# candle.net
KiCad netlist of a schematic drawn in EAGLE
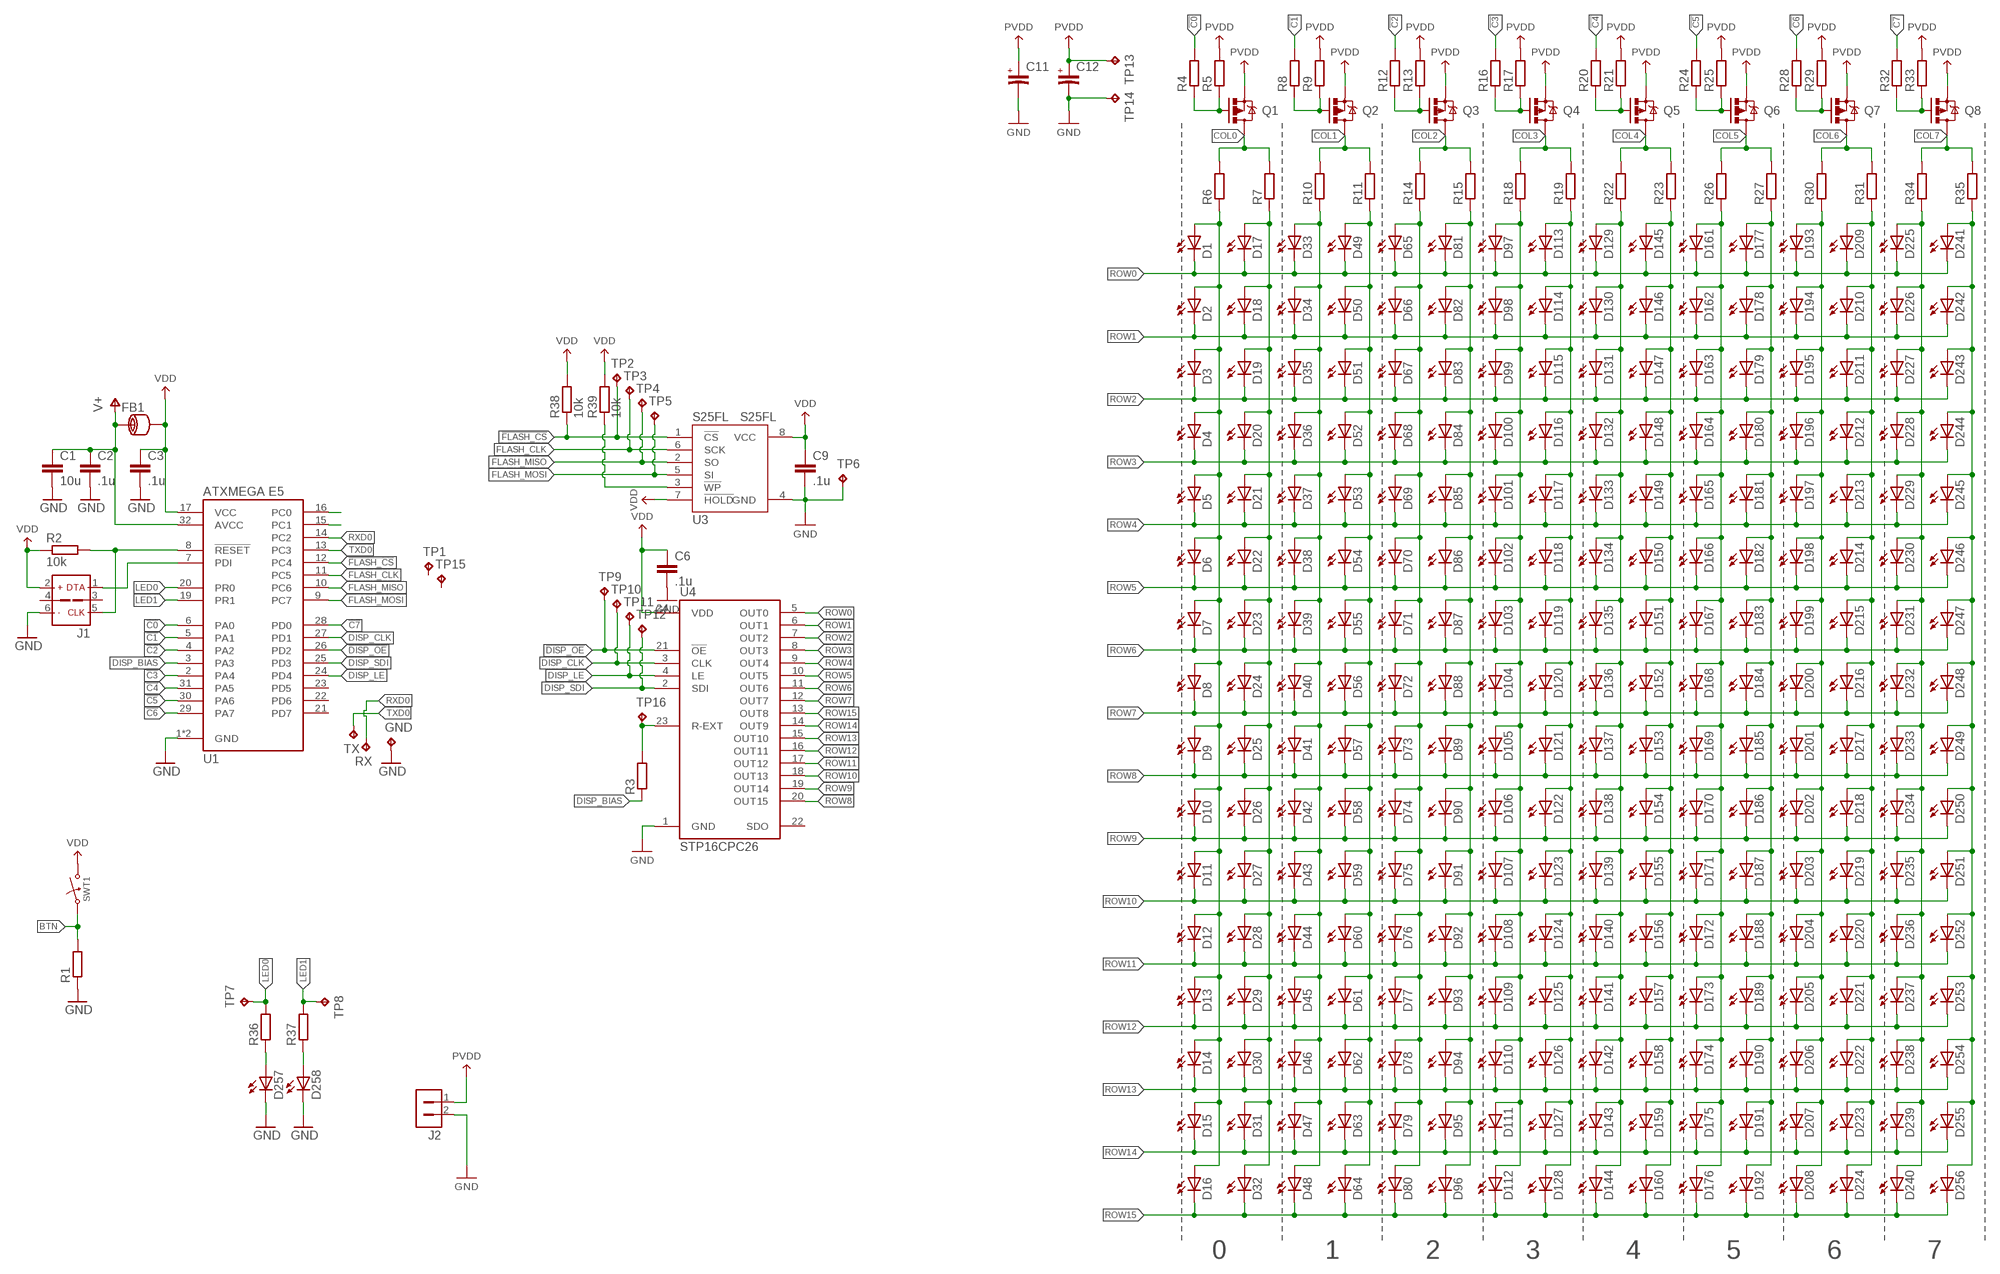
[diagram p0: schematic, sheet 1]

(export (version "E")
  (design (tool "Eeschema 10.0.6"))
  (components
    (comp (ref "C1")
      (value "10u")
      (footprint "eagle-import:0805")
      (libsource (lib "eagle-import") (part "C_0805"))
    )
    (comp (ref "C2")
      (value ".1u")
      (footprint "eagle-import:0805")
      (libsource (lib "eagle-import") (part "C_0805"))
    )
    (comp (ref "C3")
      (value ".1u")
      (footprint "eagle-import:0805")
      (libsource (lib "eagle-import") (part "C_0805"))
    )
    (comp (ref "C6")
      (value ".1u")
      (footprint "eagle-import:0805")
      (libsource (lib "eagle-import") (part "C_0805"))
    )
    (comp (ref "C9")
      (value ".1u")
      (footprint "eagle-import:0805")
      (libsource (lib "eagle-import") (part "C_0805"))
    )
    (comp (ref "C11")
      (value "C_POL_1206")
      (footprint "eagle-import:1206_POL")
      (libsource (lib "eagle-import") (part "C_POL_1206"))
    )
    (comp (ref "C12")
      (value "C_POL_1206")
      (footprint "eagle-import:1206_POL")
      (libsource (lib "eagle-import") (part "C_POL_1206"))
    )
    (comp (ref "D1")
      (value "LED_0805")
      (footprint "eagle-import:0805_LED")
      (libsource (lib "eagle-import") (part "LED_0805"))
    )
    (comp (ref "D2")
      (value "LED_0805")
      (footprint "eagle-import:0805_LED")
      (libsource (lib "eagle-import") (part "LED_0805"))
    )
    (comp (ref "D3")
      (value "LED_0805")
      (footprint "eagle-import:0805_LED")
      (libsource (lib "eagle-import") (part "LED_0805"))
    )
    (comp (ref "D4")
      (value "LED_0805")
      (footprint "eagle-import:0805_LED")
      (libsource (lib "eagle-import") (part "LED_0805"))
    )
    (comp (ref "D5")
      (value "LED_0805")
      (footprint "eagle-import:0805_LED")
      (libsource (lib "eagle-import") (part "LED_0805"))
    )
    (comp (ref "D6")
      (value "LED_0805")
      (footprint "eagle-import:0805_LED")
      (libsource (lib "eagle-import") (part "LED_0805"))
    )
    (comp (ref "D7")
      (value "LED_0805")
      (footprint "eagle-import:0805_LED")
      (libsource (lib "eagle-import") (part "LED_0805"))
    )
    (comp (ref "D8")
      (value "LED_0805")
      (footprint "eagle-import:0805_LED")
      (libsource (lib "eagle-import") (part "LED_0805"))
    )
    (comp (ref "D9")
      (value "LED_0805")
      (footprint "eagle-import:0805_LED")
      (libsource (lib "eagle-import") (part "LED_0805"))
    )
    (comp (ref "D10")
      (value "LED_0805")
      (footprint "eagle-import:0805_LED")
      (libsource (lib "eagle-import") (part "LED_0805"))
    )
    (comp (ref "D11")
      (value "LED_0805")
      (footprint "eagle-import:0805_LED")
      (libsource (lib "eagle-import") (part "LED_0805"))
    )
    (comp (ref "D12")
      (value "LED_0805")
      (footprint "eagle-import:0805_LED")
      (libsource (lib "eagle-import") (part "LED_0805"))
    )
    (comp (ref "D13")
      (value "LED_0805")
      (footprint "eagle-import:0805_LED")
      (libsource (lib "eagle-import") (part "LED_0805"))
    )
    (comp (ref "D14")
      (value "LED_0805")
      (footprint "eagle-import:0805_LED")
      (libsource (lib "eagle-import") (part "LED_0805"))
    )
    (comp (ref "D15")
      (value "LED_0805")
      (footprint "eagle-import:0805_LED")
      (libsource (lib "eagle-import") (part "LED_0805"))
    )
    (comp (ref "D16")
      (value "LED_0805")
      (footprint "eagle-import:0805_LED")
      (libsource (lib "eagle-import") (part "LED_0805"))
    )
    (comp (ref "D17")
      (value "LED_0805")
      (footprint "eagle-import:0805_LED")
      (libsource (lib "eagle-import") (part "LED_0805"))
    )
    (comp (ref "D18")
      (value "LED_0805")
      (footprint "eagle-import:0805_LED")
      (libsource (lib "eagle-import") (part "LED_0805"))
    )
    (comp (ref "D19")
      (value "LED_0805")
      (footprint "eagle-import:0805_LED")
      (libsource (lib "eagle-import") (part "LED_0805"))
    )
    (comp (ref "D20")
      (value "LED_0805")
      (footprint "eagle-import:0805_LED")
      (libsource (lib "eagle-import") (part "LED_0805"))
    )
    (comp (ref "D21")
      (value "LED_0805")
      (footprint "eagle-import:0805_LED")
      (libsource (lib "eagle-import") (part "LED_0805"))
    )
    (comp (ref "D22")
      (value "LED_0805")
      (footprint "eagle-import:0805_LED")
      (libsource (lib "eagle-import") (part "LED_0805"))
    )
    (comp (ref "D23")
      (value "LED_0805")
      (footprint "eagle-import:0805_LED")
      (libsource (lib "eagle-import") (part "LED_0805"))
    )
    (comp (ref "D24")
      (value "LED_0805")
      (footprint "eagle-import:0805_LED")
      (libsource (lib "eagle-import") (part "LED_0805"))
    )
    (comp (ref "D25")
      (value "LED_0805")
      (footprint "eagle-import:0805_LED")
      (libsource (lib "eagle-import") (part "LED_0805"))
    )
    (comp (ref "D26")
      (value "LED_0805")
      (footprint "eagle-import:0805_LED")
      (libsource (lib "eagle-import") (part "LED_0805"))
    )
    (comp (ref "D27")
      (value "LED_0805")
      (footprint "eagle-import:0805_LED")
      (libsource (lib "eagle-import") (part "LED_0805"))
    )
    (comp (ref "D28")
      (value "LED_0805")
      (footprint "eagle-import:0805_LED")
      (libsource (lib "eagle-import") (part "LED_0805"))
    )
    (comp (ref "D29")
      (value "LED_0805")
      (footprint "eagle-import:0805_LED")
      (libsource (lib "eagle-import") (part "LED_0805"))
    )
    (comp (ref "D30")
      (value "LED_0805")
      (footprint "eagle-import:0805_LED")
      (libsource (lib "eagle-import") (part "LED_0805"))
    )
    (comp (ref "D31")
      (value "LED_0805")
      (footprint "eagle-import:0805_LED")
      (libsource (lib "eagle-import") (part "LED_0805"))
    )
    (comp (ref "D32")
      (value "LED_0805")
      (footprint "eagle-import:0805_LED")
      (libsource (lib "eagle-import") (part "LED_0805"))
    )
    (comp (ref "D33")
      (value "LED_0805")
      (footprint "eagle-import:0805_LED")
      (libsource (lib "eagle-import") (part "LED_0805"))
    )
    (comp (ref "D34")
      (value "LED_0805")
      (footprint "eagle-import:0805_LED")
      (libsource (lib "eagle-import") (part "LED_0805"))
    )
    (comp (ref "D35")
      (value "LED_0805")
      (footprint "eagle-import:0805_LED")
      (libsource (lib "eagle-import") (part "LED_0805"))
    )
    (comp (ref "D36")
      (value "LED_0805")
      (footprint "eagle-import:0805_LED")
      (libsource (lib "eagle-import") (part "LED_0805"))
    )
    (comp (ref "D37")
      (value "LED_0805")
      (footprint "eagle-import:0805_LED")
      (libsource (lib "eagle-import") (part "LED_0805"))
    )
    (comp (ref "D38")
      (value "LED_0805")
      (footprint "eagle-import:0805_LED")
      (libsource (lib "eagle-import") (part "LED_0805"))
    )
    (comp (ref "D39")
      (value "LED_0805")
      (footprint "eagle-import:0805_LED")
      (libsource (lib "eagle-import") (part "LED_0805"))
    )
    (comp (ref "D40")
      (value "LED_0805")
      (footprint "eagle-import:0805_LED")
      (libsource (lib "eagle-import") (part "LED_0805"))
    )
    (comp (ref "D41")
      (value "LED_0805")
      (footprint "eagle-import:0805_LED")
      (libsource (lib "eagle-import") (part "LED_0805"))
    )
    (comp (ref "D42")
      (value "LED_0805")
      (footprint "eagle-import:0805_LED")
      (libsource (lib "eagle-import") (part "LED_0805"))
    )
    (comp (ref "D43")
      (value "LED_0805")
      (footprint "eagle-import:0805_LED")
      (libsource (lib "eagle-import") (part "LED_0805"))
    )
    (comp (ref "D44")
      (value "LED_0805")
      (footprint "eagle-import:0805_LED")
      (libsource (lib "eagle-import") (part "LED_0805"))
    )
    (comp (ref "D45")
      (value "LED_0805")
      (footprint "eagle-import:0805_LED")
      (libsource (lib "eagle-import") (part "LED_0805"))
    )
    (comp (ref "D46")
      (value "LED_0805")
      (footprint "eagle-import:0805_LED")
      (libsource (lib "eagle-import") (part "LED_0805"))
    )
    (comp (ref "D47")
      (value "LED_0805")
      (footprint "eagle-import:0805_LED")
      (libsource (lib "eagle-import") (part "LED_0805"))
    )
    (comp (ref "D48")
      (value "LED_0805")
      (footprint "eagle-import:0805_LED")
      (libsource (lib "eagle-import") (part "LED_0805"))
    )
    (comp (ref "D49")
      (value "LED_0805")
      (footprint "eagle-import:0805_LED")
      (libsource (lib "eagle-import") (part "LED_0805"))
    )
    (comp (ref "D50")
      (value "LED_0805")
      (footprint "eagle-import:0805_LED")
      (libsource (lib "eagle-import") (part "LED_0805"))
    )
    (comp (ref "D51")
      (value "LED_0805")
      (footprint "eagle-import:0805_LED")
      (libsource (lib "eagle-import") (part "LED_0805"))
    )
    (comp (ref "D52")
      (value "LED_0805")
      (footprint "eagle-import:0805_LED")
      (libsource (lib "eagle-import") (part "LED_0805"))
    )
    (comp (ref "D53")
      (value "LED_0805")
      (footprint "eagle-import:0805_LED")
      (libsource (lib "eagle-import") (part "LED_0805"))
    )
    (comp (ref "D54")
      (value "LED_0805")
      (footprint "eagle-import:0805_LED")
      (libsource (lib "eagle-import") (part "LED_0805"))
    )
    (comp (ref "D55")
      (value "LED_0805")
      (footprint "eagle-import:0805_LED")
      (libsource (lib "eagle-import") (part "LED_0805"))
    )
    (comp (ref "D56")
      (value "LED_0805")
      (footprint "eagle-import:0805_LED")
      (libsource (lib "eagle-import") (part "LED_0805"))
    )
    (comp (ref "D57")
      (value "LED_0805")
      (footprint "eagle-import:0805_LED")
      (libsource (lib "eagle-import") (part "LED_0805"))
    )
    (comp (ref "D58")
      (value "LED_0805")
      (footprint "eagle-import:0805_LED")
      (libsource (lib "eagle-import") (part "LED_0805"))
    )
    (comp (ref "D59")
      (value "LED_0805")
      (footprint "eagle-import:0805_LED")
      (libsource (lib "eagle-import") (part "LED_0805"))
    )
    (comp (ref "D60")
      (value "LED_0805")
      (footprint "eagle-import:0805_LED")
      (libsource (lib "eagle-import") (part "LED_0805"))
    )
    (comp (ref "D61")
      (value "LED_0805")
      (footprint "eagle-import:0805_LED")
      (libsource (lib "eagle-import") (part "LED_0805"))
    )
    (comp (ref "D62")
      (value "LED_0805")
      (footprint "eagle-import:0805_LED")
      (libsource (lib "eagle-import") (part "LED_0805"))
    )
    (comp (ref "D63")
      (value "LED_0805")
      (footprint "eagle-import:0805_LED")
      (libsource (lib "eagle-import") (part "LED_0805"))
    )
    (comp (ref "D64")
      (value "LED_0805")
      (footprint "eagle-import:0805_LED")
      (libsource (lib "eagle-import") (part "LED_0805"))
    )
    (comp (ref "D65")
      (value "LED_0805")
      (footprint "eagle-import:0805_LED")
      (libsource (lib "eagle-import") (part "LED_0805"))
    )
    (comp (ref "D66")
      (value "LED_0805")
      (footprint "eagle-import:0805_LED")
      (libsource (lib "eagle-import") (part "LED_0805"))
    )
    (comp (ref "D67")
      (value "LED_0805")
      (footprint "eagle-import:0805_LED")
      (libsource (lib "eagle-import") (part "LED_0805"))
    )
    (comp (ref "D68")
      (value "LED_0805")
      (footprint "eagle-import:0805_LED")
      (libsource (lib "eagle-import") (part "LED_0805"))
    )
    (comp (ref "D69")
      (value "LED_0805")
      (footprint "eagle-import:0805_LED")
      (libsource (lib "eagle-import") (part "LED_0805"))
    )
    (comp (ref "D70")
      (value "LED_0805")
      (footprint "eagle-import:0805_LED")
      (libsource (lib "eagle-import") (part "LED_0805"))
    )
    (comp (ref "D71")
      (value "LED_0805")
      (footprint "eagle-import:0805_LED")
      (libsource (lib "eagle-import") (part "LED_0805"))
    )
    (comp (ref "D72")
      (value "LED_0805")
      (footprint "eagle-import:0805_LED")
      (libsource (lib "eagle-import") (part "LED_0805"))
    )
    (comp (ref "D73")
      (value "LED_0805")
      (footprint "eagle-import:0805_LED")
      (libsource (lib "eagle-import") (part "LED_0805"))
    )
    (comp (ref "D74")
      (value "LED_0805")
      (footprint "eagle-import:0805_LED")
      (libsource (lib "eagle-import") (part "LED_0805"))
    )
    (comp (ref "D75")
      (value "LED_0805")
      (footprint "eagle-import:0805_LED")
      (libsource (lib "eagle-import") (part "LED_0805"))
    )
    (comp (ref "D76")
      (value "LED_0805")
      (footprint "eagle-import:0805_LED")
      (libsource (lib "eagle-import") (part "LED_0805"))
    )
    (comp (ref "D77")
      (value "LED_0805")
      (footprint "eagle-import:0805_LED")
      (libsource (lib "eagle-import") (part "LED_0805"))
    )
    (comp (ref "D78")
      (value "LED_0805")
      (footprint "eagle-import:0805_LED")
      (libsource (lib "eagle-import") (part "LED_0805"))
    )
    (comp (ref "D79")
      (value "LED_0805")
      (footprint "eagle-import:0805_LED")
      (libsource (lib "eagle-import") (part "LED_0805"))
    )
    (comp (ref "D80")
      (value "LED_0805")
      (footprint "eagle-import:0805_LED")
      (libsource (lib "eagle-import") (part "LED_0805"))
    )
    (comp (ref "D81")
      (value "LED_0805")
      (footprint "eagle-import:0805_LED")
      (libsource (lib "eagle-import") (part "LED_0805"))
    )
    (comp (ref "D82")
      (value "LED_0805")
      (footprint "eagle-import:0805_LED")
      (libsource (lib "eagle-import") (part "LED_0805"))
    )
    (comp (ref "D83")
      (value "LED_0805")
      (footprint "eagle-import:0805_LED")
      (libsource (lib "eagle-import") (part "LED_0805"))
    )
    (comp (ref "D84")
      (value "LED_0805")
      (footprint "eagle-import:0805_LED")
      (libsource (lib "eagle-import") (part "LED_0805"))
    )
    (comp (ref "D85")
      (value "LED_0805")
      (footprint "eagle-import:0805_LED")
      (libsource (lib "eagle-import") (part "LED_0805"))
    )
    (comp (ref "D86")
      (value "LED_0805")
      (footprint "eagle-import:0805_LED")
      (libsource (lib "eagle-import") (part "LED_0805"))
    )
    (comp (ref "D87")
      (value "LED_0805")
      (footprint "eagle-import:0805_LED")
      (libsource (lib "eagle-import") (part "LED_0805"))
    )
    (comp (ref "D88")
      (value "LED_0805")
      (footprint "eagle-import:0805_LED")
      (libsource (lib "eagle-import") (part "LED_0805"))
    )
    (comp (ref "D89")
      (value "LED_0805")
      (footprint "eagle-import:0805_LED")
      (libsource (lib "eagle-import") (part "LED_0805"))
    )
    (comp (ref "D90")
      (value "LED_0805")
      (footprint "eagle-import:0805_LED")
      (libsource (lib "eagle-import") (part "LED_0805"))
    )
    (comp (ref "D91")
      (value "LED_0805")
      (footprint "eagle-import:0805_LED")
      (libsource (lib "eagle-import") (part "LED_0805"))
    )
    (comp (ref "D92")
      (value "LED_0805")
      (footprint "eagle-import:0805_LED")
      (libsource (lib "eagle-import") (part "LED_0805"))
    )
    (comp (ref "D93")
      (value "LED_0805")
      (footprint "eagle-import:0805_LED")
      (libsource (lib "eagle-import") (part "LED_0805"))
    )
    (comp (ref "D94")
      (value "LED_0805")
      (footprint "eagle-import:0805_LED")
      (libsource (lib "eagle-import") (part "LED_0805"))
    )
    (comp (ref "D95")
      (value "LED_0805")
      (footprint "eagle-import:0805_LED")
      (libsource (lib "eagle-import") (part "LED_0805"))
    )
    (comp (ref "D96")
      (value "LED_0805")
      (footprint "eagle-import:0805_LED")
      (libsource (lib "eagle-import") (part "LED_0805"))
    )
    (comp (ref "D97")
      (value "LED_0805")
      (footprint "eagle-import:0805_LED")
      (libsource (lib "eagle-import") (part "LED_0805"))
    )
    (comp (ref "D98")
      (value "LED_0805")
      (footprint "eagle-import:0805_LED")
      (libsource (lib "eagle-import") (part "LED_0805"))
    )
    (comp (ref "D99")
      (value "LED_0805")
      (footprint "eagle-import:0805_LED")
      (libsource (lib "eagle-import") (part "LED_0805"))
    )
    (comp (ref "D100")
      (value "LED_0805")
      (footprint "eagle-import:0805_LED")
      (libsource (lib "eagle-import") (part "LED_0805"))
    )
    (comp (ref "D101")
      (value "LED_0805")
      (footprint "eagle-import:0805_LED")
      (libsource (lib "eagle-import") (part "LED_0805"))
    )
    (comp (ref "D102")
      (value "LED_0805")
      (footprint "eagle-import:0805_LED")
      (libsource (lib "eagle-import") (part "LED_0805"))
    )
    (comp (ref "D103")
      (value "LED_0805")
      (footprint "eagle-import:0805_LED")
      (libsource (lib "eagle-import") (part "LED_0805"))
    )
    (comp (ref "D104")
      (value "LED_0805")
      (footprint "eagle-import:0805_LED")
      (libsource (lib "eagle-import") (part "LED_0805"))
    )
    (comp (ref "D105")
      (value "LED_0805")
      (footprint "eagle-import:0805_LED")
      (libsource (lib "eagle-import") (part "LED_0805"))
    )
    (comp (ref "D106")
      (value "LED_0805")
      (footprint "eagle-import:0805_LED")
      (libsource (lib "eagle-import") (part "LED_0805"))
    )
    (comp (ref "D107")
      (value "LED_0805")
      (footprint "eagle-import:0805_LED")
      (libsource (lib "eagle-import") (part "LED_0805"))
    )
    (comp (ref "D108")
      (value "LED_0805")
      (footprint "eagle-import:0805_LED")
      (libsource (lib "eagle-import") (part "LED_0805"))
    )
    (comp (ref "D109")
      (value "LED_0805")
      (footprint "eagle-import:0805_LED")
      (libsource (lib "eagle-import") (part "LED_0805"))
    )
    (comp (ref "D110")
      (value "LED_0805")
      (footprint "eagle-import:0805_LED")
      (libsource (lib "eagle-import") (part "LED_0805"))
    )
    (comp (ref "D111")
      (value "LED_0805")
      (footprint "eagle-import:0805_LED")
      (libsource (lib "eagle-import") (part "LED_0805"))
    )
    (comp (ref "D112")
      (value "LED_0805")
      (footprint "eagle-import:0805_LED")
      (libsource (lib "eagle-import") (part "LED_0805"))
    )
    (comp (ref "D113")
      (value "LED_0805")
      (footprint "eagle-import:0805_LED")
      (libsource (lib "eagle-import") (part "LED_0805"))
    )
    (comp (ref "D114")
      (value "LED_0805")
      (footprint "eagle-import:0805_LED")
      (libsource (lib "eagle-import") (part "LED_0805"))
    )
    (comp (ref "D115")
      (value "LED_0805")
      (footprint "eagle-import:0805_LED")
      (libsource (lib "eagle-import") (part "LED_0805"))
    )
    (comp (ref "D116")
      (value "LED_0805")
      (footprint "eagle-import:0805_LED")
      (libsource (lib "eagle-import") (part "LED_0805"))
    )
    (comp (ref "D117")
      (value "LED_0805")
      (footprint "eagle-import:0805_LED")
      (libsource (lib "eagle-import") (part "LED_0805"))
    )
    (comp (ref "D118")
      (value "LED_0805")
      (footprint "eagle-import:0805_LED")
      (libsource (lib "eagle-import") (part "LED_0805"))
    )
    (comp (ref "D119")
      (value "LED_0805")
      (footprint "eagle-import:0805_LED")
      (libsource (lib "eagle-import") (part "LED_0805"))
    )
    (comp (ref "D120")
      (value "LED_0805")
      (footprint "eagle-import:0805_LED")
      (libsource (lib "eagle-import") (part "LED_0805"))
    )
    (comp (ref "D121")
      (value "LED_0805")
      (footprint "eagle-import:0805_LED")
      (libsource (lib "eagle-import") (part "LED_0805"))
    )
    (comp (ref "D122")
      (value "LED_0805")
      (footprint "eagle-import:0805_LED")
      (libsource (lib "eagle-import") (part "LED_0805"))
    )
    (comp (ref "D123")
      (value "LED_0805")
      (footprint "eagle-import:0805_LED")
      (libsource (lib "eagle-import") (part "LED_0805"))
    )
    (comp (ref "D124")
      (value "LED_0805")
      (footprint "eagle-import:0805_LED")
      (libsource (lib "eagle-import") (part "LED_0805"))
    )
    (comp (ref "D125")
      (value "LED_0805")
      (footprint "eagle-import:0805_LED")
      (libsource (lib "eagle-import") (part "LED_0805"))
    )
    (comp (ref "D126")
      (value "LED_0805")
      (footprint "eagle-import:0805_LED")
      (libsource (lib "eagle-import") (part "LED_0805"))
    )
    (comp (ref "D127")
      (value "LED_0805")
      (footprint "eagle-import:0805_LED")
      (libsource (lib "eagle-import") (part "LED_0805"))
    )
    (comp (ref "D128")
      (value "LED_0805")
      (footprint "eagle-import:0805_LED")
      (libsource (lib "eagle-import") (part "LED_0805"))
    )
    (comp (ref "D129")
      (value "LED_0805")
      (footprint "eagle-import:0805_LED")
      (libsource (lib "eagle-import") (part "LED_0805"))
    )
    (comp (ref "D130")
      (value "LED_0805")
      (footprint "eagle-import:0805_LED")
      (libsource (lib "eagle-import") (part "LED_0805"))
    )
    (comp (ref "D131")
      (value "LED_0805")
      (footprint "eagle-import:0805_LED")
      (libsource (lib "eagle-import") (part "LED_0805"))
    )
    (comp (ref "D132")
      (value "LED_0805")
      (footprint "eagle-import:0805_LED")
      (libsource (lib "eagle-import") (part "LED_0805"))
    )
    (comp (ref "D133")
      (value "LED_0805")
      (footprint "eagle-import:0805_LED")
      (libsource (lib "eagle-import") (part "LED_0805"))
    )
    (comp (ref "D134")
      (value "LED_0805")
      (footprint "eagle-import:0805_LED")
      (libsource (lib "eagle-import") (part "LED_0805"))
    )
    (comp (ref "D135")
      (value "LED_0805")
      (footprint "eagle-import:0805_LED")
      (libsource (lib "eagle-import") (part "LED_0805"))
    )
    (comp (ref "D136")
      (value "LED_0805")
      (footprint "eagle-import:0805_LED")
      (libsource (lib "eagle-import") (part "LED_0805"))
    )
    (comp (ref "D137")
      (value "LED_0805")
      (footprint "eagle-import:0805_LED")
      (libsource (lib "eagle-import") (part "LED_0805"))
    )
    (comp (ref "D138")
      (value "LED_0805")
      (footprint "eagle-import:0805_LED")
      (libsource (lib "eagle-import") (part "LED_0805"))
    )
    (comp (ref "D139")
      (value "LED_0805")
      (footprint "eagle-import:0805_LED")
      (libsource (lib "eagle-import") (part "LED_0805"))
    )
    (comp (ref "D140")
      (value "LED_0805")
      (footprint "eagle-import:0805_LED")
      (libsource (lib "eagle-import") (part "LED_0805"))
    )
    (comp (ref "D141")
      (value "LED_0805")
      (footprint "eagle-import:0805_LED")
      (libsource (lib "eagle-import") (part "LED_0805"))
    )
    (comp (ref "D142")
      (value "LED_0805")
      (footprint "eagle-import:0805_LED")
      (libsource (lib "eagle-import") (part "LED_0805"))
    )
    (comp (ref "D143")
      (value "LED_0805")
      (footprint "eagle-import:0805_LED")
      (libsource (lib "eagle-import") (part "LED_0805"))
    )
    (comp (ref "D144")
      (value "LED_0805")
      (footprint "eagle-import:0805_LED")
      (libsource (lib "eagle-import") (part "LED_0805"))
    )
    (comp (ref "D145")
      (value "LED_0805")
      (footprint "eagle-import:0805_LED")
      (libsource (lib "eagle-import") (part "LED_0805"))
    )
    (comp (ref "D146")
      (value "LED_0805")
      (footprint "eagle-import:0805_LED")
      (libsource (lib "eagle-import") (part "LED_0805"))
    )
    (comp (ref "D147")
      (value "LED_0805")
      (footprint "eagle-import:0805_LED")
      (libsource (lib "eagle-import") (part "LED_0805"))
    )
    (comp (ref "D148")
      (value "LED_0805")
      (footprint "eagle-import:0805_LED")
      (libsource (lib "eagle-import") (part "LED_0805"))
    )
    (comp (ref "D149")
      (value "LED_0805")
      (footprint "eagle-import:0805_LED")
      (libsource (lib "eagle-import") (part "LED_0805"))
    )
    (comp (ref "D150")
      (value "LED_0805")
      (footprint "eagle-import:0805_LED")
      (libsource (lib "eagle-import") (part "LED_0805"))
    )
    (comp (ref "D151")
      (value "LED_0805")
      (footprint "eagle-import:0805_LED")
      (libsource (lib "eagle-import") (part "LED_0805"))
    )
    (comp (ref "D152")
      (value "LED_0805")
      (footprint "eagle-import:0805_LED")
      (libsource (lib "eagle-import") (part "LED_0805"))
    )
    (comp (ref "D153")
      (value "LED_0805")
      (footprint "eagle-import:0805_LED")
      (libsource (lib "eagle-import") (part "LED_0805"))
    )
    (comp (ref "D154")
      (value "LED_0805")
      (footprint "eagle-import:0805_LED")
      (libsource (lib "eagle-import") (part "LED_0805"))
    )
    (comp (ref "D155")
      (value "LED_0805")
      (footprint "eagle-import:0805_LED")
      (libsource (lib "eagle-import") (part "LED_0805"))
    )
    (comp (ref "D156")
      (value "LED_0805")
      (footprint "eagle-import:0805_LED")
      (libsource (lib "eagle-import") (part "LED_0805"))
    )
    (comp (ref "D157")
      (value "LED_0805")
      (footprint "eagle-import:0805_LED")
      (libsource (lib "eagle-import") (part "LED_0805"))
    )
    (comp (ref "D158")
      (value "LED_0805")
      (footprint "eagle-import:0805_LED")
      (libsource (lib "eagle-import") (part "LED_0805"))
    )
    (comp (ref "D159")
      (value "LED_0805")
      (footprint "eagle-import:0805_LED")
      (libsource (lib "eagle-import") (part "LED_0805"))
    )
    (comp (ref "D160")
      (value "LED_0805")
      (footprint "eagle-import:0805_LED")
      (libsource (lib "eagle-import") (part "LED_0805"))
    )
    (comp (ref "D161")
      (value "LED_0805")
      (footprint "eagle-import:0805_LED")
      (libsource (lib "eagle-import") (part "LED_0805"))
    )
    (comp (ref "D162")
      (value "LED_0805")
      (footprint "eagle-import:0805_LED")
      (libsource (lib "eagle-import") (part "LED_0805"))
    )
    (comp (ref "D163")
      (value "LED_0805")
      (footprint "eagle-import:0805_LED")
      (libsource (lib "eagle-import") (part "LED_0805"))
    )
    (comp (ref "D164")
      (value "LED_0805")
      (footprint "eagle-import:0805_LED")
      (libsource (lib "eagle-import") (part "LED_0805"))
    )
    (comp (ref "D165")
      (value "LED_0805")
      (footprint "eagle-import:0805_LED")
      (libsource (lib "eagle-import") (part "LED_0805"))
    )
    (comp (ref "D166")
      (value "LED_0805")
      (footprint "eagle-import:0805_LED")
      (libsource (lib "eagle-import") (part "LED_0805"))
    )
    (comp (ref "D167")
      (value "LED_0805")
      (footprint "eagle-import:0805_LED")
      (libsource (lib "eagle-import") (part "LED_0805"))
    )
    (comp (ref "D168")
      (value "LED_0805")
      (footprint "eagle-import:0805_LED")
      (libsource (lib "eagle-import") (part "LED_0805"))
    )
    (comp (ref "D169")
      (value "LED_0805")
      (footprint "eagle-import:0805_LED")
      (libsource (lib "eagle-import") (part "LED_0805"))
    )
    (comp (ref "D170")
      (value "LED_0805")
      (footprint "eagle-import:0805_LED")
      (libsource (lib "eagle-import") (part "LED_0805"))
    )
    (comp (ref "D171")
      (value "LED_0805")
      (footprint "eagle-import:0805_LED")
      (libsource (lib "eagle-import") (part "LED_0805"))
    )
    (comp (ref "D172")
      (value "LED_0805")
      (footprint "eagle-import:0805_LED")
      (libsource (lib "eagle-import") (part "LED_0805"))
    )
    (comp (ref "D173")
      (value "LED_0805")
      (footprint "eagle-import:0805_LED")
      (libsource (lib "eagle-import") (part "LED_0805"))
    )
    (comp (ref "D174")
      (value "LED_0805")
      (footprint "eagle-import:0805_LED")
      (libsource (lib "eagle-import") (part "LED_0805"))
    )
    (comp (ref "D175")
      (value "LED_0805")
      (footprint "eagle-import:0805_LED")
      (libsource (lib "eagle-import") (part "LED_0805"))
    )
    (comp (ref "D176")
      (value "LED_0805")
      (footprint "eagle-import:0805_LED")
      (libsource (lib "eagle-import") (part "LED_0805"))
    )
    (comp (ref "D177")
      (value "LED_0805")
      (footprint "eagle-import:0805_LED")
      (libsource (lib "eagle-import") (part "LED_0805"))
    )
    (comp (ref "D178")
      (value "LED_0805")
      (footprint "eagle-import:0805_LED")
      (libsource (lib "eagle-import") (part "LED_0805"))
    )
    (comp (ref "D179")
      (value "LED_0805")
      (footprint "eagle-import:0805_LED")
      (libsource (lib "eagle-import") (part "LED_0805"))
    )
    (comp (ref "D180")
      (value "LED_0805")
      (footprint "eagle-import:0805_LED")
      (libsource (lib "eagle-import") (part "LED_0805"))
    )
    (comp (ref "D181")
      (value "LED_0805")
      (footprint "eagle-import:0805_LED")
      (libsource (lib "eagle-import") (part "LED_0805"))
    )
    (comp (ref "D182")
      (value "LED_0805")
      (footprint "eagle-import:0805_LED")
      (libsource (lib "eagle-import") (part "LED_0805"))
    )
    (comp (ref "D183")
      (value "LED_0805")
      (footprint "eagle-import:0805_LED")
      (libsource (lib "eagle-import") (part "LED_0805"))
    )
    (comp (ref "D184")
      (value "LED_0805")
      (footprint "eagle-import:0805_LED")
      (libsource (lib "eagle-import") (part "LED_0805"))
    )
    (comp (ref "D185")
      (value "LED_0805")
      (footprint "eagle-import:0805_LED")
      (libsource (lib "eagle-import") (part "LED_0805"))
    )
    (comp (ref "D186")
      (value "LED_0805")
      (footprint "eagle-import:0805_LED")
      (libsource (lib "eagle-import") (part "LED_0805"))
    )
    (comp (ref "D187")
      (value "LED_0805")
      (footprint "eagle-import:0805_LED")
      (libsource (lib "eagle-import") (part "LED_0805"))
    )
    (comp (ref "D188")
      (value "LED_0805")
      (footprint "eagle-import:0805_LED")
      (libsource (lib "eagle-import") (part "LED_0805"))
    )
    (comp (ref "D189")
      (value "LED_0805")
      (footprint "eagle-import:0805_LED")
      (libsource (lib "eagle-import") (part "LED_0805"))
    )
    (comp (ref "D190")
      (value "LED_0805")
      (footprint "eagle-import:0805_LED")
      (libsource (lib "eagle-import") (part "LED_0805"))
    )
    (comp (ref "D191")
      (value "LED_0805")
      (footprint "eagle-import:0805_LED")
      (libsource (lib "eagle-import") (part "LED_0805"))
    )
    (comp (ref "D192")
      (value "LED_0805")
      (footprint "eagle-import:0805_LED")
      (libsource (lib "eagle-import") (part "LED_0805"))
    )
    (comp (ref "D193")
      (value "LED_0805")
      (footprint "eagle-import:0805_LED")
      (libsource (lib "eagle-import") (part "LED_0805"))
    )
    (comp (ref "D194")
      (value "LED_0805")
      (footprint "eagle-import:0805_LED")
      (libsource (lib "eagle-import") (part "LED_0805"))
    )
    (comp (ref "D195")
      (value "LED_0805")
      (footprint "eagle-import:0805_LED")
      (libsource (lib "eagle-import") (part "LED_0805"))
    )
    (comp (ref "D196")
      (value "LED_0805")
      (footprint "eagle-import:0805_LED")
      (libsource (lib "eagle-import") (part "LED_0805"))
    )
    (comp (ref "D197")
      (value "LED_0805")
      (footprint "eagle-import:0805_LED")
      (libsource (lib "eagle-import") (part "LED_0805"))
    )
    (comp (ref "D198")
      (value "LED_0805")
      (footprint "eagle-import:0805_LED")
      (libsource (lib "eagle-import") (part "LED_0805"))
    )
    (comp (ref "D199")
      (value "LED_0805")
      (footprint "eagle-import:0805_LED")
      (libsource (lib "eagle-import") (part "LED_0805"))
    )
    (comp (ref "D200")
      (value "LED_0805")
      (footprint "eagle-import:0805_LED")
      (libsource (lib "eagle-import") (part "LED_0805"))
    )
    (comp (ref "D201")
      (value "LED_0805")
      (footprint "eagle-import:0805_LED")
      (libsource (lib "eagle-import") (part "LED_0805"))
    )
    (comp (ref "D202")
      (value "LED_0805")
      (footprint "eagle-import:0805_LED")
      (libsource (lib "eagle-import") (part "LED_0805"))
    )
    (comp (ref "D203")
      (value "LED_0805")
      (footprint "eagle-import:0805_LED")
      (libsource (lib "eagle-import") (part "LED_0805"))
    )
    (comp (ref "D204")
      (value "LED_0805")
      (footprint "eagle-import:0805_LED")
      (libsource (lib "eagle-import") (part "LED_0805"))
    )
    (comp (ref "D205")
      (value "LED_0805")
      (footprint "eagle-import:0805_LED")
      (libsource (lib "eagle-import") (part "LED_0805"))
    )
    (comp (ref "D206")
      (value "LED_0805")
      (footprint "eagle-import:0805_LED")
      (libsource (lib "eagle-import") (part "LED_0805"))
    )
    (comp (ref "D207")
      (value "LED_0805")
      (footprint "eagle-import:0805_LED")
      (libsource (lib "eagle-import") (part "LED_0805"))
    )
    (comp (ref "D208")
      (value "LED_0805")
      (footprint "eagle-import:0805_LED")
      (libsource (lib "eagle-import") (part "LED_0805"))
    )
    (comp (ref "D209")
      (value "LED_0805")
      (footprint "eagle-import:0805_LED")
      (libsource (lib "eagle-import") (part "LED_0805"))
    )
    (comp (ref "D210")
      (value "LED_0805")
      (footprint "eagle-import:0805_LED")
      (libsource (lib "eagle-import") (part "LED_0805"))
    )
    (comp (ref "D211")
      (value "LED_0805")
      (footprint "eagle-import:0805_LED")
      (libsource (lib "eagle-import") (part "LED_0805"))
    )
    (comp (ref "D212")
      (value "LED_0805")
      (footprint "eagle-import:0805_LED")
      (libsource (lib "eagle-import") (part "LED_0805"))
    )
    (comp (ref "D213")
      (value "LED_0805")
      (footprint "eagle-import:0805_LED")
      (libsource (lib "eagle-import") (part "LED_0805"))
    )
    (comp (ref "D214")
      (value "LED_0805")
      (footprint "eagle-import:0805_LED")
      (libsource (lib "eagle-import") (part "LED_0805"))
    )
    (comp (ref "D215")
      (value "LED_0805")
      (footprint "eagle-import:0805_LED")
      (libsource (lib "eagle-import") (part "LED_0805"))
    )
    (comp (ref "D216")
      (value "LED_0805")
      (footprint "eagle-import:0805_LED")
      (libsource (lib "eagle-import") (part "LED_0805"))
    )
    (comp (ref "D217")
      (value "LED_0805")
      (footprint "eagle-import:0805_LED")
      (libsource (lib "eagle-import") (part "LED_0805"))
    )
    (comp (ref "D218")
      (value "LED_0805")
      (footprint "eagle-import:0805_LED")
      (libsource (lib "eagle-import") (part "LED_0805"))
    )
    (comp (ref "D219")
      (value "LED_0805")
      (footprint "eagle-import:0805_LED")
      (libsource (lib "eagle-import") (part "LED_0805"))
    )
    (comp (ref "D220")
      (value "LED_0805")
      (footprint "eagle-import:0805_LED")
      (libsource (lib "eagle-import") (part "LED_0805"))
    )
    (comp (ref "D221")
      (value "LED_0805")
      (footprint "eagle-import:0805_LED")
      (libsource (lib "eagle-import") (part "LED_0805"))
    )
    (comp (ref "D222")
      (value "LED_0805")
      (footprint "eagle-import:0805_LED")
      (libsource (lib "eagle-import") (part "LED_0805"))
    )
    (comp (ref "D223")
      (value "LED_0805")
      (footprint "eagle-import:0805_LED")
      (libsource (lib "eagle-import") (part "LED_0805"))
    )
    (comp (ref "D224")
      (value "LED_0805")
      (footprint "eagle-import:0805_LED")
      (libsource (lib "eagle-import") (part "LED_0805"))
    )
    (comp (ref "D225")
      (value "LED_0805")
      (footprint "eagle-import:0805_LED")
      (libsource (lib "eagle-import") (part "LED_0805"))
    )
    (comp (ref "D226")
      (value "LED_0805")
      (footprint "eagle-import:0805_LED")
      (libsource (lib "eagle-import") (part "LED_0805"))
    )
    (comp (ref "D227")
      (value "LED_0805")
      (footprint "eagle-import:0805_LED")
      (libsource (lib "eagle-import") (part "LED_0805"))
    )
    (comp (ref "D228")
      (value "LED_0805")
      (footprint "eagle-import:0805_LED")
      (libsource (lib "eagle-import") (part "LED_0805"))
    )
    (comp (ref "D229")
      (value "LED_0805")
      (footprint "eagle-import:0805_LED")
      (libsource (lib "eagle-import") (part "LED_0805"))
    )
    (comp (ref "D230")
      (value "LED_0805")
      (footprint "eagle-import:0805_LED")
      (libsource (lib "eagle-import") (part "LED_0805"))
    )
    (comp (ref "D231")
      (value "LED_0805")
      (footprint "eagle-import:0805_LED")
      (libsource (lib "eagle-import") (part "LED_0805"))
    )
    (comp (ref "D232")
      (value "LED_0805")
      (footprint "eagle-import:0805_LED")
      (libsource (lib "eagle-import") (part "LED_0805"))
    )
    (comp (ref "D233")
      (value "LED_0805")
      (footprint "eagle-import:0805_LED")
      (libsource (lib "eagle-import") (part "LED_0805"))
    )
    (comp (ref "D234")
      (value "LED_0805")
      (footprint "eagle-import:0805_LED")
      (libsource (lib "eagle-import") (part "LED_0805"))
    )
    (comp (ref "D235")
      (value "LED_0805")
      (footprint "eagle-import:0805_LED")
      (libsource (lib "eagle-import") (part "LED_0805"))
    )
    (comp (ref "D236")
      (value "LED_0805")
      (footprint "eagle-import:0805_LED")
      (libsource (lib "eagle-import") (part "LED_0805"))
    )
    (comp (ref "D237")
      (value "LED_0805")
      (footprint "eagle-import:0805_LED")
      (libsource (lib "eagle-import") (part "LED_0805"))
    )
    (comp (ref "D238")
      (value "LED_0805")
      (footprint "eagle-import:0805_LED")
      (libsource (lib "eagle-import") (part "LED_0805"))
    )
    (comp (ref "D239")
      (value "LED_0805")
      (footprint "eagle-import:0805_LED")
      (libsource (lib "eagle-import") (part "LED_0805"))
    )
    (comp (ref "D240")
      (value "LED_0805")
      (footprint "eagle-import:0805_LED")
      (libsource (lib "eagle-import") (part "LED_0805"))
    )
    (comp (ref "D241")
      (value "LED_0805")
      (footprint "eagle-import:0805_LED")
      (libsource (lib "eagle-import") (part "LED_0805"))
    )
    (comp (ref "D242")
      (value "LED_0805")
      (footprint "eagle-import:0805_LED")
      (libsource (lib "eagle-import") (part "LED_0805"))
    )
    (comp (ref "D243")
      (value "LED_0805")
      (footprint "eagle-import:0805_LED")
      (libsource (lib "eagle-import") (part "LED_0805"))
    )
    (comp (ref "D244")
      (value "LED_0805")
      (footprint "eagle-import:0805_LED")
      (libsource (lib "eagle-import") (part "LED_0805"))
    )
    (comp (ref "D245")
      (value "LED_0805")
      (footprint "eagle-import:0805_LED")
      (libsource (lib "eagle-import") (part "LED_0805"))
    )
    (comp (ref "D246")
      (value "LED_0805")
      (footprint "eagle-import:0805_LED")
      (libsource (lib "eagle-import") (part "LED_0805"))
    )
    (comp (ref "D247")
      (value "LED_0805")
      (footprint "eagle-import:0805_LED")
      (libsource (lib "eagle-import") (part "LED_0805"))
    )
    (comp (ref "D248")
      (value "LED_0805")
      (footprint "eagle-import:0805_LED")
      (libsource (lib "eagle-import") (part "LED_0805"))
    )
    (comp (ref "D249")
      (value "LED_0805")
      (footprint "eagle-import:0805_LED")
      (libsource (lib "eagle-import") (part "LED_0805"))
    )
    (comp (ref "D250")
      (value "LED_0805")
      (footprint "eagle-import:0805_LED")
      (libsource (lib "eagle-import") (part "LED_0805"))
    )
    (comp (ref "D251")
      (value "LED_0805")
      (footprint "eagle-import:0805_LED")
      (libsource (lib "eagle-import") (part "LED_0805"))
    )
    (comp (ref "D252")
      (value "LED_0805")
      (footprint "eagle-import:0805_LED")
      (libsource (lib "eagle-import") (part "LED_0805"))
    )
    (comp (ref "D253")
      (value "LED_0805")
      (footprint "eagle-import:0805_LED")
      (libsource (lib "eagle-import") (part "LED_0805"))
    )
    (comp (ref "D254")
      (value "LED_0805")
      (footprint "eagle-import:0805_LED")
      (libsource (lib "eagle-import") (part "LED_0805"))
    )
    (comp (ref "D255")
      (value "LED_0805")
      (footprint "eagle-import:0805_LED")
      (libsource (lib "eagle-import") (part "LED_0805"))
    )
    (comp (ref "D256")
      (value "LED_0805")
      (footprint "eagle-import:0805_LED")
      (libsource (lib "eagle-import") (part "LED_0805"))
    )
    (comp (ref "D257")
      (value "LED_0805")
      (footprint "eagle-import:0805_LED")
      (libsource (lib "eagle-import") (part "LED_0805"))
    )
    (comp (ref "D258")
      (value "LED_0805")
      (footprint "eagle-import:0805_LED")
      (libsource (lib "eagle-import") (part "LED_0805"))
    )
    (comp (ref "FB1")
      (value "FB_0603")
      (footprint "eagle-import:0603")
      (libsource (lib "eagle-import") (part "FB_0603"))
    )
    (comp (ref "GND")
      (value "TPB1,27")
      (footprint "eagle-import:B1,27")
      (libsource (lib "eagle-import") (part "TPB1,27"))
    )
    (comp (ref "J1")
      (value "PDI_LOCK")
      (footprint "eagle-import:2X3_LOCK")
      (libsource (lib "eagle-import") (part "PDI_LOCK"))
    )
    (comp (ref "J2")
      (value "1X2_MOLEX_53254")
      (footprint "eagle-import:1X2_MOLEX_53254")
      (libsource (lib "eagle-import") (part "1X2_MOLEX_53254"))
    )
    (comp (ref "Q1")
      (value "PMV160UP")
      (footprint "eagle-import:SOT23")
      (libsource (lib "eagle-import") (part "PMV160UP"))
    )
    (comp (ref "Q2")
      (value "PMV160UP")
      (footprint "eagle-import:SOT23")
      (libsource (lib "eagle-import") (part "PMV160UP"))
    )
    (comp (ref "Q3")
      (value "PMV160UP")
      (footprint "eagle-import:SOT23")
      (libsource (lib "eagle-import") (part "PMV160UP"))
    )
    (comp (ref "Q4")
      (value "PMV160UP")
      (footprint "eagle-import:SOT23")
      (libsource (lib "eagle-import") (part "PMV160UP"))
    )
    (comp (ref "Q5")
      (value "PMV160UP")
      (footprint "eagle-import:SOT23")
      (libsource (lib "eagle-import") (part "PMV160UP"))
    )
    (comp (ref "Q6")
      (value "PMV160UP")
      (footprint "eagle-import:SOT23")
      (libsource (lib "eagle-import") (part "PMV160UP"))
    )
    (comp (ref "Q7")
      (value "PMV160UP")
      (footprint "eagle-import:SOT23")
      (libsource (lib "eagle-import") (part "PMV160UP"))
    )
    (comp (ref "Q8")
      (value "PMV160UP")
      (footprint "eagle-import:SOT23")
      (libsource (lib "eagle-import") (part "PMV160UP"))
    )
    (comp (ref "R1")
      (value "R_0603")
      (footprint "eagle-import:0603")
      (libsource (lib "eagle-import") (part "Sebastian 2_R_0603"))
    )
    (comp (ref "R2")
      (value "10k")
      (footprint "eagle-import:0805")
      (libsource (lib "eagle-import") (part "R_0805"))
    )
    (comp (ref "R3")
      (value "R_0603")
      (footprint "eagle-import:0603")
      (libsource (lib "eagle-import") (part "Sebastian 2_R_0603"))
    )
    (comp (ref "R4")
      (value "R_0603")
      (footprint "eagle-import:0603")
      (libsource (lib "eagle-import") (part "Sebastian 2_R_0603"))
    )
    (comp (ref "R5")
      (value "R_0603")
      (footprint "eagle-import:0603")
      (libsource (lib "eagle-import") (part "Sebastian 2_R_0603"))
    )
    (comp (ref "R6")
      (value "R_0603")
      (footprint "eagle-import:0603")
      (libsource (lib "eagle-import") (part "Sebastian 2_R_0603"))
    )
    (comp (ref "R7")
      (value "R_0603")
      (footprint "eagle-import:0603")
      (libsource (lib "eagle-import") (part "Sebastian 2_R_0603"))
    )
    (comp (ref "R8")
      (value "R_0603")
      (footprint "eagle-import:0603")
      (libsource (lib "eagle-import") (part "Sebastian 2_R_0603"))
    )
    (comp (ref "R9")
      (value "R_0603")
      (footprint "eagle-import:0603")
      (libsource (lib "eagle-import") (part "Sebastian 2_R_0603"))
    )
    (comp (ref "R10")
      (value "R_0603")
      (footprint "eagle-import:0603")
      (libsource (lib "eagle-import") (part "Sebastian 2_R_0603"))
    )
    (comp (ref "R11")
      (value "R_0603")
      (footprint "eagle-import:0603")
      (libsource (lib "eagle-import") (part "Sebastian 2_R_0603"))
    )
    (comp (ref "R12")
      (value "R_0603")
      (footprint "eagle-import:0603")
      (libsource (lib "eagle-import") (part "Sebastian 2_R_0603"))
    )
    (comp (ref "R13")
      (value "R_0603")
      (footprint "eagle-import:0603")
      (libsource (lib "eagle-import") (part "Sebastian 2_R_0603"))
    )
    (comp (ref "R14")
      (value "R_0603")
      (footprint "eagle-import:0603")
      (libsource (lib "eagle-import") (part "Sebastian 2_R_0603"))
    )
    (comp (ref "R15")
      (value "R_0603")
      (footprint "eagle-import:0603")
      (libsource (lib "eagle-import") (part "Sebastian 2_R_0603"))
    )
    (comp (ref "R16")
      (value "R_0603")
      (footprint "eagle-import:0603")
      (libsource (lib "eagle-import") (part "Sebastian 2_R_0603"))
    )
    (comp (ref "R17")
      (value "R_0603")
      (footprint "eagle-import:0603")
      (libsource (lib "eagle-import") (part "Sebastian 2_R_0603"))
    )
    (comp (ref "R18")
      (value "R_0603")
      (footprint "eagle-import:0603")
      (libsource (lib "eagle-import") (part "Sebastian 2_R_0603"))
    )
    (comp (ref "R19")
      (value "R_0603")
      (footprint "eagle-import:0603")
      (libsource (lib "eagle-import") (part "Sebastian 2_R_0603"))
    )
    (comp (ref "R20")
      (value "R_0603")
      (footprint "eagle-import:0603")
      (libsource (lib "eagle-import") (part "Sebastian 2_R_0603"))
    )
    (comp (ref "R21")
      (value "R_0603")
      (footprint "eagle-import:0603")
      (libsource (lib "eagle-import") (part "Sebastian 2_R_0603"))
    )
    (comp (ref "R22")
      (value "R_0603")
      (footprint "eagle-import:0603")
      (libsource (lib "eagle-import") (part "Sebastian 2_R_0603"))
    )
    (comp (ref "R23")
      (value "R_0603")
      (footprint "eagle-import:0603")
      (libsource (lib "eagle-import") (part "Sebastian 2_R_0603"))
    )
    (comp (ref "R24")
      (value "R_0603")
      (footprint "eagle-import:0603")
      (libsource (lib "eagle-import") (part "Sebastian 2_R_0603"))
    )
    (comp (ref "R25")
      (value "R_0603")
      (footprint "eagle-import:0603")
      (libsource (lib "eagle-import") (part "Sebastian 2_R_0603"))
    )
    (comp (ref "R26")
      (value "R_0603")
      (footprint "eagle-import:0603")
      (libsource (lib "eagle-import") (part "Sebastian 2_R_0603"))
    )
    (comp (ref "R27")
      (value "R_0603")
      (footprint "eagle-import:0603")
      (libsource (lib "eagle-import") (part "Sebastian 2_R_0603"))
    )
    (comp (ref "R28")
      (value "R_0603")
      (footprint "eagle-import:0603")
      (libsource (lib "eagle-import") (part "Sebastian 2_R_0603"))
    )
    (comp (ref "R29")
      (value "R_0603")
      (footprint "eagle-import:0603")
      (libsource (lib "eagle-import") (part "Sebastian 2_R_0603"))
    )
    (comp (ref "R30")
      (value "R_0603")
      (footprint "eagle-import:0603")
      (libsource (lib "eagle-import") (part "Sebastian 2_R_0603"))
    )
    (comp (ref "R31")
      (value "R_0603")
      (footprint "eagle-import:0603")
      (libsource (lib "eagle-import") (part "Sebastian 2_R_0603"))
    )
    (comp (ref "R32")
      (value "R_0603")
      (footprint "eagle-import:0603")
      (libsource (lib "eagle-import") (part "Sebastian 2_R_0603"))
    )
    (comp (ref "R33")
      (value "R_0603")
      (footprint "eagle-import:0603")
      (libsource (lib "eagle-import") (part "Sebastian 2_R_0603"))
    )
    (comp (ref "R34")
      (value "R_0603")
      (footprint "eagle-import:0603")
      (libsource (lib "eagle-import") (part "Sebastian 2_R_0603"))
    )
    (comp (ref "R35")
      (value "R_0603")
      (footprint "eagle-import:0603")
      (libsource (lib "eagle-import") (part "Sebastian 2_R_0603"))
    )
    (comp (ref "R36")
      (value "R_0603")
      (footprint "eagle-import:0603")
      (libsource (lib "eagle-import") (part "Sebastian 2_R_0603"))
    )
    (comp (ref "R37")
      (value "R_0603")
      (footprint "eagle-import:0603")
      (libsource (lib "eagle-import") (part "Sebastian 2_R_0603"))
    )
    (comp (ref "R38")
      (value "10k")
      (footprint "eagle-import:0603")
      (libsource (lib "eagle-import") (part "Sebastian 2_R_0603"))
    )
    (comp (ref "R39")
      (value "10k")
      (footprint "eagle-import:0603")
      (libsource (lib "eagle-import") (part "Sebastian 2_R_0603"))
    )
    (comp (ref "RX")
      (value "TPB1,27")
      (footprint "eagle-import:B1,27")
      (libsource (lib "eagle-import") (part "TPB1,27"))
    )
    (comp (ref "SWT1")
      (value "BUTTON_SMD_2P")
      (footprint "eagle-import:BTN_SMD_2PIN")
      (libsource (lib "eagle-import") (part "BUTTON_SMD_2P"))
    )
    (comp (ref "TP1")
      (value "TPB1,27")
      (footprint "eagle-import:B1,27")
      (libsource (lib "eagle-import") (part "TPB1,27"))
    )
    (comp (ref "TP2")
      (value "TPB1,27")
      (footprint "eagle-import:B1,27")
      (libsource (lib "eagle-import") (part "TPB1,27"))
    )
    (comp (ref "TP3")
      (value "TPB1,27")
      (footprint "eagle-import:B1,27")
      (libsource (lib "eagle-import") (part "TPB1,27"))
    )
    (comp (ref "TP4")
      (value "TPB1,27")
      (footprint "eagle-import:B1,27")
      (libsource (lib "eagle-import") (part "TPB1,27"))
    )
    (comp (ref "TP5")
      (value "TPB1,27")
      (footprint "eagle-import:B1,27")
      (libsource (lib "eagle-import") (part "TPB1,27"))
    )
    (comp (ref "TP6")
      (value "TPB1,27")
      (footprint "eagle-import:B1,27")
      (libsource (lib "eagle-import") (part "TPB1,27"))
    )
    (comp (ref "TP7")
      (value "TPB1,27")
      (footprint "eagle-import:B1,27")
      (libsource (lib "eagle-import") (part "TPB1,27"))
    )
    (comp (ref "TP8")
      (value "TPB1,27")
      (footprint "eagle-import:B1,27")
      (libsource (lib "eagle-import") (part "TPB1,27"))
    )
    (comp (ref "TP9")
      (value "TPB1,27")
      (footprint "eagle-import:B1,27")
      (libsource (lib "eagle-import") (part "TPB1,27"))
    )
    (comp (ref "TP10")
      (value "TPB1,27")
      (footprint "eagle-import:B1,27")
      (libsource (lib "eagle-import") (part "TPB1,27"))
    )
    (comp (ref "TP11")
      (value "TPB1,27")
      (footprint "eagle-import:B1,27")
      (libsource (lib "eagle-import") (part "TPB1,27"))
    )
    (comp (ref "TP12")
      (value "TPB1,27")
      (footprint "eagle-import:B1,27")
      (libsource (lib "eagle-import") (part "TPB1,27"))
    )
    (comp (ref "TP13")
      (value "TPB1,27")
      (footprint "eagle-import:B1,27")
      (libsource (lib "eagle-import") (part "TPB1,27"))
    )
    (comp (ref "TP14")
      (value "TPB1,27")
      (footprint "eagle-import:B1,27")
      (libsource (lib "eagle-import") (part "TPB1,27"))
    )
    (comp (ref "TP15")
      (value "TPB1,27")
      (footprint "eagle-import:B1,27")
      (libsource (lib "eagle-import") (part "TPB1,27"))
    )
    (comp (ref "TP16")
      (value "TPB1,27")
      (footprint "eagle-import:B1,27")
      (libsource (lib "eagle-import") (part "TPB1,27"))
    )
    (comp (ref "TX")
      (value "TPB1,27")
      (footprint "eagle-import:B1,27")
      (libsource (lib "eagle-import") (part "TPB1,27"))
    )
    (comp (ref "U1")
      (value "ATXMEGA_E5_TQFP")
      (footprint "eagle-import:TQFP32")
      (libsource (lib "eagle-import") (part "ATXMEGA_E5_TQFP"))
    )
    (comp (ref "U3")
      (value "S25FL")
      (footprint "eagle-import:SO8")
      (libsource (lib "eagle-import") (part "S25FL"))
    )
    (comp (ref "U4")
      (value "STP16CPC26TSSOP24")
      (footprint "eagle-import:TSSOP24")
      (libsource (lib "eagle-import") (part "STP16CPC26TSSOP24"))
    )
  )
  (nets
    (net (code "1") (name "/~{C0}") (class "Default")
      (node (ref "R4") (pin "2") (pinfunction "2_2") (pintype "passive"))
      (node (ref "U1") (pin "6") (pinfunction "PA0_6") (pintype "bidirectional"))
    )
    (net (code "2") (name "/~{C1}") (class "Default")
      (node (ref "R8") (pin "2") (pinfunction "2_2") (pintype "passive"))
      (node (ref "U1") (pin "5") (pinfunction "PA1_5") (pintype "bidirectional"))
    )
    (net (code "3") (name "/~{C2}") (class "Default")
      (node (ref "R12") (pin "2") (pinfunction "2_2") (pintype "passive"))
      (node (ref "U1") (pin "4") (pinfunction "PA2_4") (pintype "bidirectional"))
    )
    (net (code "4") (name "/~{C3}") (class "Default")
      (node (ref "R16") (pin "2") (pinfunction "2_2") (pintype "passive"))
      (node (ref "U1") (pin "2") (pinfunction "PA4_2") (pintype "bidirectional"))
    )
    (net (code "5") (name "/~{C4}") (class "Default")
      (node (ref "R20") (pin "2") (pinfunction "2_2") (pintype "passive"))
      (node (ref "U1") (pin "31") (pinfunction "PA5_31") (pintype "bidirectional"))
    )
    (net (code "6") (name "/~{C5}") (class "Default")
      (node (ref "R24") (pin "2") (pinfunction "2_2") (pintype "passive"))
      (node (ref "U1") (pin "30") (pinfunction "PA6_30") (pintype "bidirectional"))
    )
    (net (code "7") (name "/~{C6}") (class "Default")
      (node (ref "R28") (pin "2") (pinfunction "2_2") (pintype "passive"))
      (node (ref "U1") (pin "29") (pinfunction "PA7_29") (pintype "bidirectional"))
    )
    (net (code "8") (name "/~{C7}") (class "Default")
      (node (ref "R32") (pin "2") (pinfunction "2_2") (pintype "passive"))
      (node (ref "U1") (pin "28") (pinfunction "PD0_28") (pintype "bidirectional"))
    )
    (net (code "9") (name "/~{DISP_OE}") (class "Default")
      (node (ref "TP9") (pin "TP") (pinfunction "TP_TP") (pintype "input"))
      (node (ref "U1") (pin "26") (pinfunction "PD2_26") (pintype "bidirectional"))
      (node (ref "U4") (pin "21") (pinfunction "~{OE}_21") (pintype "bidirectional"))
    )
    (net (code "10") (name "/~{FLASH_CS}") (class "Default")
      (node (ref "R38") (pin "1") (pinfunction "1_1") (pintype "passive"))
      (node (ref "TP2") (pin "TP") (pinfunction "TP_TP") (pintype "input"))
      (node (ref "U1") (pin "12") (pinfunction "PC4_12") (pintype "bidirectional"))
      (node (ref "U3") (pin "1") (pinfunction "~{CS}_1") (pintype "bidirectional"))
    )
    (net (code "11") (name "BTN") (class "Default")
      (node (ref "R1") (pin "2") (pinfunction "2_2") (pintype "passive"))
      (node (ref "SWT1") (pin "1") (pinfunction "P$1_1") (pintype "bidirectional"))
    )
    (net (code "12") (name "COL0") (class "Default")
      (node (ref "Q1") (pin "3") (pinfunction "D_3") (pintype "passive"))
      (node (ref "R6") (pin "2") (pinfunction "2_2") (pintype "passive"))
      (node (ref "R7") (pin "2") (pinfunction "2_2") (pintype "passive"))
    )
    (net (code "13") (name "COL1") (class "Default")
      (node (ref "Q2") (pin "3") (pinfunction "D_3") (pintype "passive"))
      (node (ref "R10") (pin "2") (pinfunction "2_2") (pintype "passive"))
      (node (ref "R11") (pin "2") (pinfunction "2_2") (pintype "passive"))
    )
    (net (code "14") (name "COL2") (class "Default")
      (node (ref "Q3") (pin "3") (pinfunction "D_3") (pintype "passive"))
      (node (ref "R14") (pin "2") (pinfunction "2_2") (pintype "passive"))
      (node (ref "R15") (pin "2") (pinfunction "2_2") (pintype "passive"))
    )
    (net (code "15") (name "COL3") (class "Default")
      (node (ref "Q4") (pin "3") (pinfunction "D_3") (pintype "passive"))
      (node (ref "R18") (pin "2") (pinfunction "2_2") (pintype "passive"))
      (node (ref "R19") (pin "2") (pinfunction "2_2") (pintype "passive"))
    )
    (net (code "16") (name "COL4") (class "Default")
      (node (ref "Q5") (pin "3") (pinfunction "D_3") (pintype "passive"))
      (node (ref "R22") (pin "2") (pinfunction "2_2") (pintype "passive"))
      (node (ref "R23") (pin "2") (pinfunction "2_2") (pintype "passive"))
    )
    (net (code "17") (name "COL5") (class "Default")
      (node (ref "Q6") (pin "3") (pinfunction "D_3") (pintype "passive"))
      (node (ref "R26") (pin "2") (pinfunction "2_2") (pintype "passive"))
      (node (ref "R27") (pin "2") (pinfunction "2_2") (pintype "passive"))
    )
    (net (code "18") (name "COL6") (class "Default")
      (node (ref "Q7") (pin "3") (pinfunction "D_3") (pintype "passive"))
      (node (ref "R30") (pin "2") (pinfunction "2_2") (pintype "passive"))
      (node (ref "R31") (pin "2") (pinfunction "2_2") (pintype "passive"))
    )
    (net (code "19") (name "COL7") (class "Default")
      (node (ref "Q8") (pin "3") (pinfunction "D_3") (pintype "passive"))
      (node (ref "R34") (pin "2") (pinfunction "2_2") (pintype "passive"))
      (node (ref "R35") (pin "2") (pinfunction "2_2") (pintype "passive"))
    )
    (net (code "20") (name "DISP_BIAS") (class "Default")
      (node (ref "R3") (pin "1") (pinfunction "1_1") (pintype "passive"))
      (node (ref "U1") (pin "3") (pinfunction "PA3_3") (pintype "bidirectional"))
    )
    (net (code "21") (name "DISP_CLK") (class "Default")
      (node (ref "TP10") (pin "TP") (pinfunction "TP_TP") (pintype "input"))
      (node (ref "U1") (pin "27") (pinfunction "PD1_27") (pintype "bidirectional"))
      (node (ref "U4") (pin "3") (pinfunction "CLK_3") (pintype "bidirectional"))
    )
    (net (code "22") (name "DISP_LE") (class "Default")
      (node (ref "TP11") (pin "TP") (pinfunction "TP_TP") (pintype "input"))
      (node (ref "U1") (pin "24") (pinfunction "PD4_24") (pintype "bidirectional"))
      (node (ref "U4") (pin "4") (pinfunction "LE_4") (pintype "bidirectional"))
    )
    (net (code "23") (name "DISP_SDI") (class "Default")
      (node (ref "TP12") (pin "TP") (pinfunction "TP_TP") (pintype "input"))
      (node (ref "U1") (pin "25") (pinfunction "PD3_25") (pintype "bidirectional"))
      (node (ref "U4") (pin "2") (pinfunction "SDI_2") (pintype "bidirectional"))
    )
    (net (code "24") (name "FLASH_CLK") (class "Default")
      (node (ref "TP3") (pin "TP") (pinfunction "TP_TP") (pintype "input"))
      (node (ref "U1") (pin "11") (pinfunction "PC5_11") (pintype "bidirectional"))
      (node (ref "U3") (pin "6") (pinfunction "SCK_6") (pintype "bidirectional"))
    )
    (net (code "25") (name "FLASH_MISO") (class "Default")
      (node (ref "TP4") (pin "TP") (pinfunction "TP_TP") (pintype "input"))
      (node (ref "U1") (pin "10") (pinfunction "PC6_10") (pintype "bidirectional"))
      (node (ref "U3") (pin "2") (pinfunction "SO_2") (pintype "bidirectional"))
    )
    (net (code "26") (name "FLASH_MOSI") (class "Default")
      (node (ref "TP5") (pin "TP") (pinfunction "TP_TP") (pintype "input"))
      (node (ref "U1") (pin "9") (pinfunction "PC7_9") (pintype "bidirectional"))
      (node (ref "U3") (pin "5") (pinfunction "SI_5") (pintype "bidirectional"))
    )
    (net (code "27") (name "GND") (class "Default")
      (node (ref "C1") (pin "2") (pinfunction "2_2") (pintype "passive"))
      (node (ref "C11") (pin "2") (pinfunction "2_2") (pintype "passive"))
      (node (ref "C12") (pin "2") (pinfunction "2_2") (pintype "passive"))
      (node (ref "C2") (pin "2") (pinfunction "2_2") (pintype "passive"))
      (node (ref "C3") (pin "2") (pinfunction "2_2") (pintype "passive"))
      (node (ref "C6") (pin "2") (pinfunction "2_2") (pintype "passive"))
      (node (ref "C9") (pin "2") (pinfunction "2_2") (pintype "passive"))
      (node (ref "D257") (pin "C") (pinfunction "C_C") (pintype "passive"))
      (node (ref "D258") (pin "C") (pinfunction "C_C") (pintype "passive"))
      (node (ref "GND") (pin "TP") (pinfunction "TP_TP") (pintype "input"))
      (node (ref "J1") (pin "6") (pinfunction "GND_6") (pintype "bidirectional"))
      (node (ref "J2") (pin "2") (pinfunction "2_2") (pintype "bidirectional"))
      (node (ref "R1") (pin "1") (pinfunction "1_1") (pintype "passive"))
      (node (ref "TP14") (pin "TP") (pinfunction "TP_TP") (pintype "input"))
      (node (ref "TP6") (pin "TP") (pinfunction "TP_TP") (pintype "input"))
      (node (ref "U1") (pin "1") (pinfunction "GND_1") (pintype "bidirectional"))
      (node (ref "U1") (pin "18") (pinfunction "GND_18") (pintype "bidirectional"))
      (node (ref "U3") (pin "4") (pinfunction "GND_4") (pintype "bidirectional"))
      (node (ref "U4") (pin "1") (pinfunction "GND_1") (pintype "bidirectional"))
    )
    (net (code "28") (name "LED0") (class "Default")
      (node (ref "R36") (pin "2") (pinfunction "2_2") (pintype "passive"))
      (node (ref "TP7") (pin "TP") (pinfunction "TP_TP") (pintype "input"))
      (node (ref "U1") (pin "20") (pinfunction "PR0_20") (pintype "bidirectional"))
    )
    (net (code "29") (name "LED1") (class "Default")
      (node (ref "R37") (pin "2") (pinfunction "2_2") (pintype "passive"))
      (node (ref "TP8") (pin "TP") (pinfunction "TP_TP") (pintype "input"))
      (node (ref "U1") (pin "19") (pinfunction "PR1_19") (pintype "bidirectional"))
    )
    (net (code "30") (name "Net-(D1-PadA)") (class "Default")
      (node (ref "D1") (pin "A") (pinfunction "A_A") (pintype "passive"))
      (node (ref "D10") (pin "A") (pinfunction "A_A") (pintype "passive"))
      (node (ref "D11") (pin "A") (pinfunction "A_A") (pintype "passive"))
      (node (ref "D12") (pin "A") (pinfunction "A_A") (pintype "passive"))
      (node (ref "D13") (pin "A") (pinfunction "A_A") (pintype "passive"))
      (node (ref "D14") (pin "A") (pinfunction "A_A") (pintype "passive"))
      (node (ref "D15") (pin "A") (pinfunction "A_A") (pintype "passive"))
      (node (ref "D16") (pin "A") (pinfunction "A_A") (pintype "passive"))
      (node (ref "D2") (pin "A") (pinfunction "A_A") (pintype "passive"))
      (node (ref "D3") (pin "A") (pinfunction "A_A") (pintype "passive"))
      (node (ref "D4") (pin "A") (pinfunction "A_A") (pintype "passive"))
      (node (ref "D5") (pin "A") (pinfunction "A_A") (pintype "passive"))
      (node (ref "D6") (pin "A") (pinfunction "A_A") (pintype "passive"))
      (node (ref "D7") (pin "A") (pinfunction "A_A") (pintype "passive"))
      (node (ref "D8") (pin "A") (pinfunction "A_A") (pintype "passive"))
      (node (ref "D9") (pin "A") (pinfunction "A_A") (pintype "passive"))
      (node (ref "R6") (pin "1") (pinfunction "1_1") (pintype "passive"))
    )
    (net (code "31") (name "Net-(D17-PadA)") (class "Default")
      (node (ref "D17") (pin "A") (pinfunction "A_A") (pintype "passive"))
      (node (ref "D18") (pin "A") (pinfunction "A_A") (pintype "passive"))
      (node (ref "D19") (pin "A") (pinfunction "A_A") (pintype "passive"))
      (node (ref "D20") (pin "A") (pinfunction "A_A") (pintype "passive"))
      (node (ref "D21") (pin "A") (pinfunction "A_A") (pintype "passive"))
      (node (ref "D22") (pin "A") (pinfunction "A_A") (pintype "passive"))
      (node (ref "D23") (pin "A") (pinfunction "A_A") (pintype "passive"))
      (node (ref "D24") (pin "A") (pinfunction "A_A") (pintype "passive"))
      (node (ref "D25") (pin "A") (pinfunction "A_A") (pintype "passive"))
      (node (ref "D26") (pin "A") (pinfunction "A_A") (pintype "passive"))
      (node (ref "D27") (pin "A") (pinfunction "A_A") (pintype "passive"))
      (node (ref "D28") (pin "A") (pinfunction "A_A") (pintype "passive"))
      (node (ref "D29") (pin "A") (pinfunction "A_A") (pintype "passive"))
      (node (ref "D30") (pin "A") (pinfunction "A_A") (pintype "passive"))
      (node (ref "D31") (pin "A") (pinfunction "A_A") (pintype "passive"))
      (node (ref "D32") (pin "A") (pinfunction "A_A") (pintype "passive"))
      (node (ref "R7") (pin "1") (pinfunction "1_1") (pintype "passive"))
    )
    (net (code "32") (name "Net-(D33-PadA)") (class "Default")
      (node (ref "D33") (pin "A") (pinfunction "A_A") (pintype "passive"))
      (node (ref "D34") (pin "A") (pinfunction "A_A") (pintype "passive"))
      (node (ref "D35") (pin "A") (pinfunction "A_A") (pintype "passive"))
      (node (ref "D36") (pin "A") (pinfunction "A_A") (pintype "passive"))
      (node (ref "D37") (pin "A") (pinfunction "A_A") (pintype "passive"))
      (node (ref "D38") (pin "A") (pinfunction "A_A") (pintype "passive"))
      (node (ref "D39") (pin "A") (pinfunction "A_A") (pintype "passive"))
      (node (ref "D40") (pin "A") (pinfunction "A_A") (pintype "passive"))
      (node (ref "D41") (pin "A") (pinfunction "A_A") (pintype "passive"))
      (node (ref "D42") (pin "A") (pinfunction "A_A") (pintype "passive"))
      (node (ref "D43") (pin "A") (pinfunction "A_A") (pintype "passive"))
      (node (ref "D44") (pin "A") (pinfunction "A_A") (pintype "passive"))
      (node (ref "D45") (pin "A") (pinfunction "A_A") (pintype "passive"))
      (node (ref "D46") (pin "A") (pinfunction "A_A") (pintype "passive"))
      (node (ref "D47") (pin "A") (pinfunction "A_A") (pintype "passive"))
      (node (ref "D48") (pin "A") (pinfunction "A_A") (pintype "passive"))
      (node (ref "R10") (pin "1") (pinfunction "1_1") (pintype "passive"))
    )
    (net (code "33") (name "Net-(D49-PadA)") (class "Default")
      (node (ref "D49") (pin "A") (pinfunction "A_A") (pintype "passive"))
      (node (ref "D50") (pin "A") (pinfunction "A_A") (pintype "passive"))
      (node (ref "D51") (pin "A") (pinfunction "A_A") (pintype "passive"))
      (node (ref "D52") (pin "A") (pinfunction "A_A") (pintype "passive"))
      (node (ref "D53") (pin "A") (pinfunction "A_A") (pintype "passive"))
      (node (ref "D54") (pin "A") (pinfunction "A_A") (pintype "passive"))
      (node (ref "D55") (pin "A") (pinfunction "A_A") (pintype "passive"))
      (node (ref "D56") (pin "A") (pinfunction "A_A") (pintype "passive"))
      (node (ref "D57") (pin "A") (pinfunction "A_A") (pintype "passive"))
      (node (ref "D58") (pin "A") (pinfunction "A_A") (pintype "passive"))
      (node (ref "D59") (pin "A") (pinfunction "A_A") (pintype "passive"))
      (node (ref "D60") (pin "A") (pinfunction "A_A") (pintype "passive"))
      (node (ref "D61") (pin "A") (pinfunction "A_A") (pintype "passive"))
      (node (ref "D62") (pin "A") (pinfunction "A_A") (pintype "passive"))
      (node (ref "D63") (pin "A") (pinfunction "A_A") (pintype "passive"))
      (node (ref "D64") (pin "A") (pinfunction "A_A") (pintype "passive"))
      (node (ref "R11") (pin "1") (pinfunction "1_1") (pintype "passive"))
    )
    (net (code "34") (name "Net-(D65-PadA)") (class "Default")
      (node (ref "D65") (pin "A") (pinfunction "A_A") (pintype "passive"))
      (node (ref "D66") (pin "A") (pinfunction "A_A") (pintype "passive"))
      (node (ref "D67") (pin "A") (pinfunction "A_A") (pintype "passive"))
      (node (ref "D68") (pin "A") (pinfunction "A_A") (pintype "passive"))
      (node (ref "D69") (pin "A") (pinfunction "A_A") (pintype "passive"))
      (node (ref "D70") (pin "A") (pinfunction "A_A") (pintype "passive"))
      (node (ref "D71") (pin "A") (pinfunction "A_A") (pintype "passive"))
      (node (ref "D72") (pin "A") (pinfunction "A_A") (pintype "passive"))
      (node (ref "D73") (pin "A") (pinfunction "A_A") (pintype "passive"))
      (node (ref "D74") (pin "A") (pinfunction "A_A") (pintype "passive"))
      (node (ref "D75") (pin "A") (pinfunction "A_A") (pintype "passive"))
      (node (ref "D76") (pin "A") (pinfunction "A_A") (pintype "passive"))
      (node (ref "D77") (pin "A") (pinfunction "A_A") (pintype "passive"))
      (node (ref "D78") (pin "A") (pinfunction "A_A") (pintype "passive"))
      (node (ref "D79") (pin "A") (pinfunction "A_A") (pintype "passive"))
      (node (ref "D80") (pin "A") (pinfunction "A_A") (pintype "passive"))
      (node (ref "R14") (pin "1") (pinfunction "1_1") (pintype "passive"))
    )
    (net (code "35") (name "Net-(D81-PadA)") (class "Default")
      (node (ref "D81") (pin "A") (pinfunction "A_A") (pintype "passive"))
      (node (ref "D82") (pin "A") (pinfunction "A_A") (pintype "passive"))
      (node (ref "D83") (pin "A") (pinfunction "A_A") (pintype "passive"))
      (node (ref "D84") (pin "A") (pinfunction "A_A") (pintype "passive"))
      (node (ref "D85") (pin "A") (pinfunction "A_A") (pintype "passive"))
      (node (ref "D86") (pin "A") (pinfunction "A_A") (pintype "passive"))
      (node (ref "D87") (pin "A") (pinfunction "A_A") (pintype "passive"))
      (node (ref "D88") (pin "A") (pinfunction "A_A") (pintype "passive"))
      (node (ref "D89") (pin "A") (pinfunction "A_A") (pintype "passive"))
      (node (ref "D90") (pin "A") (pinfunction "A_A") (pintype "passive"))
      (node (ref "D91") (pin "A") (pinfunction "A_A") (pintype "passive"))
      (node (ref "D92") (pin "A") (pinfunction "A_A") (pintype "passive"))
      (node (ref "D93") (pin "A") (pinfunction "A_A") (pintype "passive"))
      (node (ref "D94") (pin "A") (pinfunction "A_A") (pintype "passive"))
      (node (ref "D95") (pin "A") (pinfunction "A_A") (pintype "passive"))
      (node (ref "D96") (pin "A") (pinfunction "A_A") (pintype "passive"))
      (node (ref "R15") (pin "1") (pinfunction "1_1") (pintype "passive"))
    )
    (net (code "36") (name "Net-(D100-PadA)") (class "Default")
      (node (ref "D100") (pin "A") (pinfunction "A_A") (pintype "passive"))
      (node (ref "D101") (pin "A") (pinfunction "A_A") (pintype "passive"))
      (node (ref "D102") (pin "A") (pinfunction "A_A") (pintype "passive"))
      (node (ref "D103") (pin "A") (pinfunction "A_A") (pintype "passive"))
      (node (ref "D104") (pin "A") (pinfunction "A_A") (pintype "passive"))
      (node (ref "D105") (pin "A") (pinfunction "A_A") (pintype "passive"))
      (node (ref "D106") (pin "A") (pinfunction "A_A") (pintype "passive"))
      (node (ref "D107") (pin "A") (pinfunction "A_A") (pintype "passive"))
      (node (ref "D108") (pin "A") (pinfunction "A_A") (pintype "passive"))
      (node (ref "D109") (pin "A") (pinfunction "A_A") (pintype "passive"))
      (node (ref "D110") (pin "A") (pinfunction "A_A") (pintype "passive"))
      (node (ref "D111") (pin "A") (pinfunction "A_A") (pintype "passive"))
      (node (ref "D112") (pin "A") (pinfunction "A_A") (pintype "passive"))
      (node (ref "D97") (pin "A") (pinfunction "A_A") (pintype "passive"))
      (node (ref "D98") (pin "A") (pinfunction "A_A") (pintype "passive"))
      (node (ref "D99") (pin "A") (pinfunction "A_A") (pintype "passive"))
      (node (ref "R18") (pin "1") (pinfunction "1_1") (pintype "passive"))
    )
    (net (code "37") (name "Net-(D113-PadA)") (class "Default")
      (node (ref "D113") (pin "A") (pinfunction "A_A") (pintype "passive"))
      (node (ref "D114") (pin "A") (pinfunction "A_A") (pintype "passive"))
      (node (ref "D115") (pin "A") (pinfunction "A_A") (pintype "passive"))
      (node (ref "D116") (pin "A") (pinfunction "A_A") (pintype "passive"))
      (node (ref "D117") (pin "A") (pinfunction "A_A") (pintype "passive"))
      (node (ref "D118") (pin "A") (pinfunction "A_A") (pintype "passive"))
      (node (ref "D119") (pin "A") (pinfunction "A_A") (pintype "passive"))
      (node (ref "D120") (pin "A") (pinfunction "A_A") (pintype "passive"))
      (node (ref "D121") (pin "A") (pinfunction "A_A") (pintype "passive"))
      (node (ref "D122") (pin "A") (pinfunction "A_A") (pintype "passive"))
      (node (ref "D123") (pin "A") (pinfunction "A_A") (pintype "passive"))
      (node (ref "D124") (pin "A") (pinfunction "A_A") (pintype "passive"))
      (node (ref "D125") (pin "A") (pinfunction "A_A") (pintype "passive"))
      (node (ref "D126") (pin "A") (pinfunction "A_A") (pintype "passive"))
      (node (ref "D127") (pin "A") (pinfunction "A_A") (pintype "passive"))
      (node (ref "D128") (pin "A") (pinfunction "A_A") (pintype "passive"))
      (node (ref "R19") (pin "1") (pinfunction "1_1") (pintype "passive"))
    )
    (net (code "38") (name "Net-(D129-PadA)") (class "Default")
      (node (ref "D129") (pin "A") (pinfunction "A_A") (pintype "passive"))
      (node (ref "D130") (pin "A") (pinfunction "A_A") (pintype "passive"))
      (node (ref "D131") (pin "A") (pinfunction "A_A") (pintype "passive"))
      (node (ref "D132") (pin "A") (pinfunction "A_A") (pintype "passive"))
      (node (ref "D133") (pin "A") (pinfunction "A_A") (pintype "passive"))
      (node (ref "D134") (pin "A") (pinfunction "A_A") (pintype "passive"))
      (node (ref "D135") (pin "A") (pinfunction "A_A") (pintype "passive"))
      (node (ref "D136") (pin "A") (pinfunction "A_A") (pintype "passive"))
      (node (ref "D137") (pin "A") (pinfunction "A_A") (pintype "passive"))
      (node (ref "D138") (pin "A") (pinfunction "A_A") (pintype "passive"))
      (node (ref "D139") (pin "A") (pinfunction "A_A") (pintype "passive"))
      (node (ref "D140") (pin "A") (pinfunction "A_A") (pintype "passive"))
      (node (ref "D141") (pin "A") (pinfunction "A_A") (pintype "passive"))
      (node (ref "D142") (pin "A") (pinfunction "A_A") (pintype "passive"))
      (node (ref "D143") (pin "A") (pinfunction "A_A") (pintype "passive"))
      (node (ref "D144") (pin "A") (pinfunction "A_A") (pintype "passive"))
      (node (ref "R22") (pin "1") (pinfunction "1_1") (pintype "passive"))
    )
    (net (code "39") (name "Net-(D145-PadA)") (class "Default")
      (node (ref "D145") (pin "A") (pinfunction "A_A") (pintype "passive"))
      (node (ref "D146") (pin "A") (pinfunction "A_A") (pintype "passive"))
      (node (ref "D147") (pin "A") (pinfunction "A_A") (pintype "passive"))
      (node (ref "D148") (pin "A") (pinfunction "A_A") (pintype "passive"))
      (node (ref "D149") (pin "A") (pinfunction "A_A") (pintype "passive"))
      (node (ref "D150") (pin "A") (pinfunction "A_A") (pintype "passive"))
      (node (ref "D151") (pin "A") (pinfunction "A_A") (pintype "passive"))
      (node (ref "D152") (pin "A") (pinfunction "A_A") (pintype "passive"))
      (node (ref "D153") (pin "A") (pinfunction "A_A") (pintype "passive"))
      (node (ref "D154") (pin "A") (pinfunction "A_A") (pintype "passive"))
      (node (ref "D155") (pin "A") (pinfunction "A_A") (pintype "passive"))
      (node (ref "D156") (pin "A") (pinfunction "A_A") (pintype "passive"))
      (node (ref "D157") (pin "A") (pinfunction "A_A") (pintype "passive"))
      (node (ref "D158") (pin "A") (pinfunction "A_A") (pintype "passive"))
      (node (ref "D159") (pin "A") (pinfunction "A_A") (pintype "passive"))
      (node (ref "D160") (pin "A") (pinfunction "A_A") (pintype "passive"))
      (node (ref "R23") (pin "1") (pinfunction "1_1") (pintype "passive"))
    )
    (net (code "40") (name "Net-(D161-PadA)") (class "Default")
      (node (ref "D161") (pin "A") (pinfunction "A_A") (pintype "passive"))
      (node (ref "D162") (pin "A") (pinfunction "A_A") (pintype "passive"))
      (node (ref "D163") (pin "A") (pinfunction "A_A") (pintype "passive"))
      (node (ref "D164") (pin "A") (pinfunction "A_A") (pintype "passive"))
      (node (ref "D165") (pin "A") (pinfunction "A_A") (pintype "passive"))
      (node (ref "D166") (pin "A") (pinfunction "A_A") (pintype "passive"))
      (node (ref "D167") (pin "A") (pinfunction "A_A") (pintype "passive"))
      (node (ref "D168") (pin "A") (pinfunction "A_A") (pintype "passive"))
      (node (ref "D169") (pin "A") (pinfunction "A_A") (pintype "passive"))
      (node (ref "D170") (pin "A") (pinfunction "A_A") (pintype "passive"))
      (node (ref "D171") (pin "A") (pinfunction "A_A") (pintype "passive"))
      (node (ref "D172") (pin "A") (pinfunction "A_A") (pintype "passive"))
      (node (ref "D173") (pin "A") (pinfunction "A_A") (pintype "passive"))
      (node (ref "D174") (pin "A") (pinfunction "A_A") (pintype "passive"))
      (node (ref "D175") (pin "A") (pinfunction "A_A") (pintype "passive"))
      (node (ref "D176") (pin "A") (pinfunction "A_A") (pintype "passive"))
      (node (ref "R26") (pin "1") (pinfunction "1_1") (pintype "passive"))
    )
    (net (code "41") (name "Net-(D177-PadA)") (class "Default")
      (node (ref "D177") (pin "A") (pinfunction "A_A") (pintype "passive"))
      (node (ref "D178") (pin "A") (pinfunction "A_A") (pintype "passive"))
      (node (ref "D179") (pin "A") (pinfunction "A_A") (pintype "passive"))
      (node (ref "D180") (pin "A") (pinfunction "A_A") (pintype "passive"))
      (node (ref "D181") (pin "A") (pinfunction "A_A") (pintype "passive"))
      (node (ref "D182") (pin "A") (pinfunction "A_A") (pintype "passive"))
      (node (ref "D183") (pin "A") (pinfunction "A_A") (pintype "passive"))
      (node (ref "D184") (pin "A") (pinfunction "A_A") (pintype "passive"))
      (node (ref "D185") (pin "A") (pinfunction "A_A") (pintype "passive"))
      (node (ref "D186") (pin "A") (pinfunction "A_A") (pintype "passive"))
      (node (ref "D187") (pin "A") (pinfunction "A_A") (pintype "passive"))
      (node (ref "D188") (pin "A") (pinfunction "A_A") (pintype "passive"))
      (node (ref "D189") (pin "A") (pinfunction "A_A") (pintype "passive"))
      (node (ref "D190") (pin "A") (pinfunction "A_A") (pintype "passive"))
      (node (ref "D191") (pin "A") (pinfunction "A_A") (pintype "passive"))
      (node (ref "D192") (pin "A") (pinfunction "A_A") (pintype "passive"))
      (node (ref "R27") (pin "1") (pinfunction "1_1") (pintype "passive"))
    )
    (net (code "42") (name "Net-(D193-PadA)") (class "Default")
      (node (ref "D193") (pin "A") (pinfunction "A_A") (pintype "passive"))
      (node (ref "D194") (pin "A") (pinfunction "A_A") (pintype "passive"))
      (node (ref "D195") (pin "A") (pinfunction "A_A") (pintype "passive"))
      (node (ref "D196") (pin "A") (pinfunction "A_A") (pintype "passive"))
      (node (ref "D197") (pin "A") (pinfunction "A_A") (pintype "passive"))
      (node (ref "D198") (pin "A") (pinfunction "A_A") (pintype "passive"))
      (node (ref "D199") (pin "A") (pinfunction "A_A") (pintype "passive"))
      (node (ref "D200") (pin "A") (pinfunction "A_A") (pintype "passive"))
      (node (ref "D201") (pin "A") (pinfunction "A_A") (pintype "passive"))
      (node (ref "D202") (pin "A") (pinfunction "A_A") (pintype "passive"))
      (node (ref "D203") (pin "A") (pinfunction "A_A") (pintype "passive"))
      (node (ref "D204") (pin "A") (pinfunction "A_A") (pintype "passive"))
      (node (ref "D205") (pin "A") (pinfunction "A_A") (pintype "passive"))
      (node (ref "D206") (pin "A") (pinfunction "A_A") (pintype "passive"))
      (node (ref "D207") (pin "A") (pinfunction "A_A") (pintype "passive"))
      (node (ref "D208") (pin "A") (pinfunction "A_A") (pintype "passive"))
      (node (ref "R30") (pin "1") (pinfunction "1_1") (pintype "passive"))
    )
    (net (code "43") (name "Net-(D209-PadA)") (class "Default")
      (node (ref "D209") (pin "A") (pinfunction "A_A") (pintype "passive"))
      (node (ref "D210") (pin "A") (pinfunction "A_A") (pintype "passive"))
      (node (ref "D211") (pin "A") (pinfunction "A_A") (pintype "passive"))
      (node (ref "D212") (pin "A") (pinfunction "A_A") (pintype "passive"))
      (node (ref "D213") (pin "A") (pinfunction "A_A") (pintype "passive"))
      (node (ref "D214") (pin "A") (pinfunction "A_A") (pintype "passive"))
      (node (ref "D215") (pin "A") (pinfunction "A_A") (pintype "passive"))
      (node (ref "D216") (pin "A") (pinfunction "A_A") (pintype "passive"))
      (node (ref "D217") (pin "A") (pinfunction "A_A") (pintype "passive"))
      (node (ref "D218") (pin "A") (pinfunction "A_A") (pintype "passive"))
      (node (ref "D219") (pin "A") (pinfunction "A_A") (pintype "passive"))
      (node (ref "D220") (pin "A") (pinfunction "A_A") (pintype "passive"))
      (node (ref "D221") (pin "A") (pinfunction "A_A") (pintype "passive"))
      (node (ref "D222") (pin "A") (pinfunction "A_A") (pintype "passive"))
      (node (ref "D223") (pin "A") (pinfunction "A_A") (pintype "passive"))
      (node (ref "D224") (pin "A") (pinfunction "A_A") (pintype "passive"))
      (node (ref "R31") (pin "1") (pinfunction "1_1") (pintype "passive"))
    )
    (net (code "44") (name "Net-(D225-PadA)") (class "Default")
      (node (ref "D225") (pin "A") (pinfunction "A_A") (pintype "passive"))
      (node (ref "D226") (pin "A") (pinfunction "A_A") (pintype "passive"))
      (node (ref "D227") (pin "A") (pinfunction "A_A") (pintype "passive"))
      (node (ref "D228") (pin "A") (pinfunction "A_A") (pintype "passive"))
      (node (ref "D229") (pin "A") (pinfunction "A_A") (pintype "passive"))
      (node (ref "D230") (pin "A") (pinfunction "A_A") (pintype "passive"))
      (node (ref "D231") (pin "A") (pinfunction "A_A") (pintype "passive"))
      (node (ref "D232") (pin "A") (pinfunction "A_A") (pintype "passive"))
      (node (ref "D233") (pin "A") (pinfunction "A_A") (pintype "passive"))
      (node (ref "D234") (pin "A") (pinfunction "A_A") (pintype "passive"))
      (node (ref "D235") (pin "A") (pinfunction "A_A") (pintype "passive"))
      (node (ref "D236") (pin "A") (pinfunction "A_A") (pintype "passive"))
      (node (ref "D237") (pin "A") (pinfunction "A_A") (pintype "passive"))
      (node (ref "D238") (pin "A") (pinfunction "A_A") (pintype "passive"))
      (node (ref "D239") (pin "A") (pinfunction "A_A") (pintype "passive"))
      (node (ref "D240") (pin "A") (pinfunction "A_A") (pintype "passive"))
      (node (ref "R34") (pin "1") (pinfunction "1_1") (pintype "passive"))
    )
    (net (code "45") (name "Net-(D241-PadA)") (class "Default")
      (node (ref "D241") (pin "A") (pinfunction "A_A") (pintype "passive"))
      (node (ref "D242") (pin "A") (pinfunction "A_A") (pintype "passive"))
      (node (ref "D243") (pin "A") (pinfunction "A_A") (pintype "passive"))
      (node (ref "D244") (pin "A") (pinfunction "A_A") (pintype "passive"))
      (node (ref "D245") (pin "A") (pinfunction "A_A") (pintype "passive"))
      (node (ref "D246") (pin "A") (pinfunction "A_A") (pintype "passive"))
      (node (ref "D247") (pin "A") (pinfunction "A_A") (pintype "passive"))
      (node (ref "D248") (pin "A") (pinfunction "A_A") (pintype "passive"))
      (node (ref "D249") (pin "A") (pinfunction "A_A") (pintype "passive"))
      (node (ref "D250") (pin "A") (pinfunction "A_A") (pintype "passive"))
      (node (ref "D251") (pin "A") (pinfunction "A_A") (pintype "passive"))
      (node (ref "D252") (pin "A") (pinfunction "A_A") (pintype "passive"))
      (node (ref "D253") (pin "A") (pinfunction "A_A") (pintype "passive"))
      (node (ref "D254") (pin "A") (pinfunction "A_A") (pintype "passive"))
      (node (ref "D255") (pin "A") (pinfunction "A_A") (pintype "passive"))
      (node (ref "D256") (pin "A") (pinfunction "A_A") (pintype "passive"))
      (node (ref "R35") (pin "1") (pinfunction "1_1") (pintype "passive"))
    )
    (net (code "46") (name "Net-(D257-PadA)") (class "Default")
      (node (ref "D257") (pin "A") (pinfunction "A_A") (pintype "passive"))
      (node (ref "R36") (pin "1") (pinfunction "1_1") (pintype "passive"))
    )
    (net (code "47") (name "Net-(D258-PadA)") (class "Default")
      (node (ref "D258") (pin "A") (pinfunction "A_A") (pintype "passive"))
      (node (ref "R37") (pin "1") (pinfunction "1_1") (pintype "passive"))
    )
    (net (code "48") (name "Net-(J1-CLK)") (class "Default")
      (node (ref "J1") (pin "5") (pinfunction "CLK_5") (pintype "bidirectional"))
      (node (ref "R2") (pin "2") (pinfunction "2_2") (pintype "passive"))
      (node (ref "U1") (pin "8") (pinfunction "~{RESET}_8") (pintype "bidirectional"))
    )
    (net (code "49") (name "Net-(J1-DATA)") (class "Default")
      (node (ref "J1") (pin "1") (pinfunction "DATA_1") (pintype "bidirectional"))
      (node (ref "U1") (pin "7") (pinfunction "PDI_7") (pintype "bidirectional"))
    )
    (net (code "50") (name "Net-(Q1-G)") (class "Default")
      (node (ref "Q1") (pin "1") (pinfunction "G_1") (pintype "passive"))
      (node (ref "R4") (pin "1") (pinfunction "1_1") (pintype "passive"))
      (node (ref "R5") (pin "1") (pinfunction "1_1") (pintype "passive"))
    )
    (net (code "51") (name "Net-(Q2-G)") (class "Default")
      (node (ref "Q2") (pin "1") (pinfunction "G_1") (pintype "passive"))
      (node (ref "R8") (pin "1") (pinfunction "1_1") (pintype "passive"))
      (node (ref "R9") (pin "1") (pinfunction "1_1") (pintype "passive"))
    )
    (net (code "52") (name "Net-(Q3-G)") (class "Default")
      (node (ref "Q3") (pin "1") (pinfunction "G_1") (pintype "passive"))
      (node (ref "R12") (pin "1") (pinfunction "1_1") (pintype "passive"))
      (node (ref "R13") (pin "1") (pinfunction "1_1") (pintype "passive"))
    )
    (net (code "53") (name "Net-(Q4-G)") (class "Default")
      (node (ref "Q4") (pin "1") (pinfunction "G_1") (pintype "passive"))
      (node (ref "R16") (pin "1") (pinfunction "1_1") (pintype "passive"))
      (node (ref "R17") (pin "1") (pinfunction "1_1") (pintype "passive"))
    )
    (net (code "54") (name "Net-(Q5-G)") (class "Default")
      (node (ref "Q5") (pin "1") (pinfunction "G_1") (pintype "passive"))
      (node (ref "R20") (pin "1") (pinfunction "1_1") (pintype "passive"))
      (node (ref "R21") (pin "1") (pinfunction "1_1") (pintype "passive"))
    )
    (net (code "55") (name "Net-(Q6-G)") (class "Default")
      (node (ref "Q6") (pin "1") (pinfunction "G_1") (pintype "passive"))
      (node (ref "R24") (pin "1") (pinfunction "1_1") (pintype "passive"))
      (node (ref "R25") (pin "1") (pinfunction "1_1") (pintype "passive"))
    )
    (net (code "56") (name "Net-(Q7-G)") (class "Default")
      (node (ref "Q7") (pin "1") (pinfunction "G_1") (pintype "passive"))
      (node (ref "R28") (pin "1") (pinfunction "1_1") (pintype "passive"))
      (node (ref "R29") (pin "1") (pinfunction "1_1") (pintype "passive"))
    )
    (net (code "57") (name "Net-(Q8-G)") (class "Default")
      (node (ref "Q8") (pin "1") (pinfunction "G_1") (pintype "passive"))
      (node (ref "R32") (pin "1") (pinfunction "1_1") (pintype "passive"))
      (node (ref "R33") (pin "1") (pinfunction "1_1") (pintype "passive"))
    )
    (net (code "58") (name "Net-(U3-~{WP})") (class "Default")
      (node (ref "R39") (pin "1") (pinfunction "1_1") (pintype "passive"))
      (node (ref "U3") (pin "3") (pinfunction "~{WP}_3") (pintype "bidirectional"))
    )
    (net (code "59") (name "Net-(U4-R-EXT)") (class "Default")
      (node (ref "R3") (pin "2") (pinfunction "2_2") (pintype "passive"))
      (node (ref "TP16") (pin "TP") (pinfunction "TP_TP") (pintype "input"))
      (node (ref "U4") (pin "23") (pinfunction "R-EXT_23") (pintype "bidirectional"))
    )
    (net (code "60") (name "PVDD") (class "Default")
      (node (ref "C11") (pin "1") (pinfunction "1_1") (pintype "passive"))
      (node (ref "C12") (pin "1") (pinfunction "1_1") (pintype "passive"))
      (node (ref "J2") (pin "1") (pinfunction "1_1") (pintype "bidirectional"))
      (node (ref "Q1") (pin "2") (pinfunction "S_2") (pintype "passive"))
      (node (ref "Q2") (pin "2") (pinfunction "S_2") (pintype "passive"))
      (node (ref "Q3") (pin "2") (pinfunction "S_2") (pintype "passive"))
      (node (ref "Q4") (pin "2") (pinfunction "S_2") (pintype "passive"))
      (node (ref "Q5") (pin "2") (pinfunction "S_2") (pintype "passive"))
      (node (ref "Q6") (pin "2") (pinfunction "S_2") (pintype "passive"))
      (node (ref "Q7") (pin "2") (pinfunction "S_2") (pintype "passive"))
      (node (ref "Q8") (pin "2") (pinfunction "S_2") (pintype "passive"))
      (node (ref "R13") (pin "2") (pinfunction "2_2") (pintype "passive"))
      (node (ref "R17") (pin "2") (pinfunction "2_2") (pintype "passive"))
      (node (ref "R21") (pin "2") (pinfunction "2_2") (pintype "passive"))
      (node (ref "R25") (pin "2") (pinfunction "2_2") (pintype "passive"))
      (node (ref "R29") (pin "2") (pinfunction "2_2") (pintype "passive"))
      (node (ref "R33") (pin "2") (pinfunction "2_2") (pintype "passive"))
      (node (ref "R5") (pin "2") (pinfunction "2_2") (pintype "passive"))
      (node (ref "R9") (pin "2") (pinfunction "2_2") (pintype "passive"))
      (node (ref "TP13") (pin "TP") (pinfunction "TP_TP") (pintype "input"))
    )
    (net (code "61") (name "ROW0") (class "Default")
      (node (ref "D1") (pin "C") (pinfunction "C_C") (pintype "passive"))
      (node (ref "D113") (pin "C") (pinfunction "C_C") (pintype "passive"))
      (node (ref "D129") (pin "C") (pinfunction "C_C") (pintype "passive"))
      (node (ref "D145") (pin "C") (pinfunction "C_C") (pintype "passive"))
      (node (ref "D161") (pin "C") (pinfunction "C_C") (pintype "passive"))
      (node (ref "D17") (pin "C") (pinfunction "C_C") (pintype "passive"))
      (node (ref "D177") (pin "C") (pinfunction "C_C") (pintype "passive"))
      (node (ref "D193") (pin "C") (pinfunction "C_C") (pintype "passive"))
      (node (ref "D209") (pin "C") (pinfunction "C_C") (pintype "passive"))
      (node (ref "D225") (pin "C") (pinfunction "C_C") (pintype "passive"))
      (node (ref "D241") (pin "C") (pinfunction "C_C") (pintype "passive"))
      (node (ref "D33") (pin "C") (pinfunction "C_C") (pintype "passive"))
      (node (ref "D49") (pin "C") (pinfunction "C_C") (pintype "passive"))
      (node (ref "D65") (pin "C") (pinfunction "C_C") (pintype "passive"))
      (node (ref "D81") (pin "C") (pinfunction "C_C") (pintype "passive"))
      (node (ref "D97") (pin "C") (pinfunction "C_C") (pintype "passive"))
      (node (ref "U4") (pin "5") (pinfunction "OUT0_5") (pintype "bidirectional"))
    )
    (net (code "62") (name "ROW1") (class "Default")
      (node (ref "D114") (pin "C") (pinfunction "C_C") (pintype "passive"))
      (node (ref "D130") (pin "C") (pinfunction "C_C") (pintype "passive"))
      (node (ref "D146") (pin "C") (pinfunction "C_C") (pintype "passive"))
      (node (ref "D162") (pin "C") (pinfunction "C_C") (pintype "passive"))
      (node (ref "D178") (pin "C") (pinfunction "C_C") (pintype "passive"))
      (node (ref "D18") (pin "C") (pinfunction "C_C") (pintype "passive"))
      (node (ref "D194") (pin "C") (pinfunction "C_C") (pintype "passive"))
      (node (ref "D2") (pin "C") (pinfunction "C_C") (pintype "passive"))
      (node (ref "D210") (pin "C") (pinfunction "C_C") (pintype "passive"))
      (node (ref "D226") (pin "C") (pinfunction "C_C") (pintype "passive"))
      (node (ref "D242") (pin "C") (pinfunction "C_C") (pintype "passive"))
      (node (ref "D34") (pin "C") (pinfunction "C_C") (pintype "passive"))
      (node (ref "D50") (pin "C") (pinfunction "C_C") (pintype "passive"))
      (node (ref "D66") (pin "C") (pinfunction "C_C") (pintype "passive"))
      (node (ref "D82") (pin "C") (pinfunction "C_C") (pintype "passive"))
      (node (ref "D98") (pin "C") (pinfunction "C_C") (pintype "passive"))
      (node (ref "U4") (pin "6") (pinfunction "OUT1_6") (pintype "bidirectional"))
    )
    (net (code "63") (name "ROW2") (class "Default")
      (node (ref "D115") (pin "C") (pinfunction "C_C") (pintype "passive"))
      (node (ref "D131") (pin "C") (pinfunction "C_C") (pintype "passive"))
      (node (ref "D147") (pin "C") (pinfunction "C_C") (pintype "passive"))
      (node (ref "D163") (pin "C") (pinfunction "C_C") (pintype "passive"))
      (node (ref "D179") (pin "C") (pinfunction "C_C") (pintype "passive"))
      (node (ref "D19") (pin "C") (pinfunction "C_C") (pintype "passive"))
      (node (ref "D195") (pin "C") (pinfunction "C_C") (pintype "passive"))
      (node (ref "D211") (pin "C") (pinfunction "C_C") (pintype "passive"))
      (node (ref "D227") (pin "C") (pinfunction "C_C") (pintype "passive"))
      (node (ref "D243") (pin "C") (pinfunction "C_C") (pintype "passive"))
      (node (ref "D3") (pin "C") (pinfunction "C_C") (pintype "passive"))
      (node (ref "D35") (pin "C") (pinfunction "C_C") (pintype "passive"))
      (node (ref "D51") (pin "C") (pinfunction "C_C") (pintype "passive"))
      (node (ref "D67") (pin "C") (pinfunction "C_C") (pintype "passive"))
      (node (ref "D83") (pin "C") (pinfunction "C_C") (pintype "passive"))
      (node (ref "D99") (pin "C") (pinfunction "C_C") (pintype "passive"))
      (node (ref "U4") (pin "7") (pinfunction "OUT2_7") (pintype "bidirectional"))
    )
    (net (code "64") (name "ROW3") (class "Default")
      (node (ref "D100") (pin "C") (pinfunction "C_C") (pintype "passive"))
      (node (ref "D116") (pin "C") (pinfunction "C_C") (pintype "passive"))
      (node (ref "D132") (pin "C") (pinfunction "C_C") (pintype "passive"))
      (node (ref "D148") (pin "C") (pinfunction "C_C") (pintype "passive"))
      (node (ref "D164") (pin "C") (pinfunction "C_C") (pintype "passive"))
      (node (ref "D180") (pin "C") (pinfunction "C_C") (pintype "passive"))
      (node (ref "D196") (pin "C") (pinfunction "C_C") (pintype "passive"))
      (node (ref "D20") (pin "C") (pinfunction "C_C") (pintype "passive"))
      (node (ref "D212") (pin "C") (pinfunction "C_C") (pintype "passive"))
      (node (ref "D228") (pin "C") (pinfunction "C_C") (pintype "passive"))
      (node (ref "D244") (pin "C") (pinfunction "C_C") (pintype "passive"))
      (node (ref "D36") (pin "C") (pinfunction "C_C") (pintype "passive"))
      (node (ref "D4") (pin "C") (pinfunction "C_C") (pintype "passive"))
      (node (ref "D52") (pin "C") (pinfunction "C_C") (pintype "passive"))
      (node (ref "D68") (pin "C") (pinfunction "C_C") (pintype "passive"))
      (node (ref "D84") (pin "C") (pinfunction "C_C") (pintype "passive"))
      (node (ref "U4") (pin "8") (pinfunction "OUT3_8") (pintype "bidirectional"))
    )
    (net (code "65") (name "ROW4") (class "Default")
      (node (ref "D101") (pin "C") (pinfunction "C_C") (pintype "passive"))
      (node (ref "D117") (pin "C") (pinfunction "C_C") (pintype "passive"))
      (node (ref "D133") (pin "C") (pinfunction "C_C") (pintype "passive"))
      (node (ref "D149") (pin "C") (pinfunction "C_C") (pintype "passive"))
      (node (ref "D165") (pin "C") (pinfunction "C_C") (pintype "passive"))
      (node (ref "D181") (pin "C") (pinfunction "C_C") (pintype "passive"))
      (node (ref "D197") (pin "C") (pinfunction "C_C") (pintype "passive"))
      (node (ref "D21") (pin "C") (pinfunction "C_C") (pintype "passive"))
      (node (ref "D213") (pin "C") (pinfunction "C_C") (pintype "passive"))
      (node (ref "D229") (pin "C") (pinfunction "C_C") (pintype "passive"))
      (node (ref "D245") (pin "C") (pinfunction "C_C") (pintype "passive"))
      (node (ref "D37") (pin "C") (pinfunction "C_C") (pintype "passive"))
      (node (ref "D5") (pin "C") (pinfunction "C_C") (pintype "passive"))
      (node (ref "D53") (pin "C") (pinfunction "C_C") (pintype "passive"))
      (node (ref "D69") (pin "C") (pinfunction "C_C") (pintype "passive"))
      (node (ref "D85") (pin "C") (pinfunction "C_C") (pintype "passive"))
      (node (ref "U4") (pin "9") (pinfunction "OUT4_9") (pintype "bidirectional"))
    )
    (net (code "66") (name "ROW5") (class "Default")
      (node (ref "D102") (pin "C") (pinfunction "C_C") (pintype "passive"))
      (node (ref "D118") (pin "C") (pinfunction "C_C") (pintype "passive"))
      (node (ref "D134") (pin "C") (pinfunction "C_C") (pintype "passive"))
      (node (ref "D150") (pin "C") (pinfunction "C_C") (pintype "passive"))
      (node (ref "D166") (pin "C") (pinfunction "C_C") (pintype "passive"))
      (node (ref "D182") (pin "C") (pinfunction "C_C") (pintype "passive"))
      (node (ref "D198") (pin "C") (pinfunction "C_C") (pintype "passive"))
      (node (ref "D214") (pin "C") (pinfunction "C_C") (pintype "passive"))
      (node (ref "D22") (pin "C") (pinfunction "C_C") (pintype "passive"))
      (node (ref "D230") (pin "C") (pinfunction "C_C") (pintype "passive"))
      (node (ref "D246") (pin "C") (pinfunction "C_C") (pintype "passive"))
      (node (ref "D38") (pin "C") (pinfunction "C_C") (pintype "passive"))
      (node (ref "D54") (pin "C") (pinfunction "C_C") (pintype "passive"))
      (node (ref "D6") (pin "C") (pinfunction "C_C") (pintype "passive"))
      (node (ref "D70") (pin "C") (pinfunction "C_C") (pintype "passive"))
      (node (ref "D86") (pin "C") (pinfunction "C_C") (pintype "passive"))
      (node (ref "U4") (pin "10") (pinfunction "OUT5_10") (pintype "bidirectional"))
    )
    (net (code "67") (name "ROW6") (class "Default")
      (node (ref "D103") (pin "C") (pinfunction "C_C") (pintype "passive"))
      (node (ref "D119") (pin "C") (pinfunction "C_C") (pintype "passive"))
      (node (ref "D135") (pin "C") (pinfunction "C_C") (pintype "passive"))
      (node (ref "D151") (pin "C") (pinfunction "C_C") (pintype "passive"))
      (node (ref "D167") (pin "C") (pinfunction "C_C") (pintype "passive"))
      (node (ref "D183") (pin "C") (pinfunction "C_C") (pintype "passive"))
      (node (ref "D199") (pin "C") (pinfunction "C_C") (pintype "passive"))
      (node (ref "D215") (pin "C") (pinfunction "C_C") (pintype "passive"))
      (node (ref "D23") (pin "C") (pinfunction "C_C") (pintype "passive"))
      (node (ref "D231") (pin "C") (pinfunction "C_C") (pintype "passive"))
      (node (ref "D247") (pin "C") (pinfunction "C_C") (pintype "passive"))
      (node (ref "D39") (pin "C") (pinfunction "C_C") (pintype "passive"))
      (node (ref "D55") (pin "C") (pinfunction "C_C") (pintype "passive"))
      (node (ref "D7") (pin "C") (pinfunction "C_C") (pintype "passive"))
      (node (ref "D71") (pin "C") (pinfunction "C_C") (pintype "passive"))
      (node (ref "D87") (pin "C") (pinfunction "C_C") (pintype "passive"))
      (node (ref "U4") (pin "11") (pinfunction "OUT6_11") (pintype "bidirectional"))
    )
    (net (code "68") (name "ROW7") (class "Default")
      (node (ref "D104") (pin "C") (pinfunction "C_C") (pintype "passive"))
      (node (ref "D120") (pin "C") (pinfunction "C_C") (pintype "passive"))
      (node (ref "D136") (pin "C") (pinfunction "C_C") (pintype "passive"))
      (node (ref "D152") (pin "C") (pinfunction "C_C") (pintype "passive"))
      (node (ref "D168") (pin "C") (pinfunction "C_C") (pintype "passive"))
      (node (ref "D184") (pin "C") (pinfunction "C_C") (pintype "passive"))
      (node (ref "D200") (pin "C") (pinfunction "C_C") (pintype "passive"))
      (node (ref "D216") (pin "C") (pinfunction "C_C") (pintype "passive"))
      (node (ref "D232") (pin "C") (pinfunction "C_C") (pintype "passive"))
      (node (ref "D24") (pin "C") (pinfunction "C_C") (pintype "passive"))
      (node (ref "D248") (pin "C") (pinfunction "C_C") (pintype "passive"))
      (node (ref "D40") (pin "C") (pinfunction "C_C") (pintype "passive"))
      (node (ref "D56") (pin "C") (pinfunction "C_C") (pintype "passive"))
      (node (ref "D72") (pin "C") (pinfunction "C_C") (pintype "passive"))
      (node (ref "D8") (pin "C") (pinfunction "C_C") (pintype "passive"))
      (node (ref "D88") (pin "C") (pinfunction "C_C") (pintype "passive"))
      (node (ref "U4") (pin "12") (pinfunction "OUT7_12") (pintype "bidirectional"))
    )
    (net (code "69") (name "ROW8") (class "Default")
      (node (ref "D105") (pin "C") (pinfunction "C_C") (pintype "passive"))
      (node (ref "D121") (pin "C") (pinfunction "C_C") (pintype "passive"))
      (node (ref "D137") (pin "C") (pinfunction "C_C") (pintype "passive"))
      (node (ref "D153") (pin "C") (pinfunction "C_C") (pintype "passive"))
      (node (ref "D169") (pin "C") (pinfunction "C_C") (pintype "passive"))
      (node (ref "D185") (pin "C") (pinfunction "C_C") (pintype "passive"))
      (node (ref "D201") (pin "C") (pinfunction "C_C") (pintype "passive"))
      (node (ref "D217") (pin "C") (pinfunction "C_C") (pintype "passive"))
      (node (ref "D233") (pin "C") (pinfunction "C_C") (pintype "passive"))
      (node (ref "D249") (pin "C") (pinfunction "C_C") (pintype "passive"))
      (node (ref "D25") (pin "C") (pinfunction "C_C") (pintype "passive"))
      (node (ref "D41") (pin "C") (pinfunction "C_C") (pintype "passive"))
      (node (ref "D57") (pin "C") (pinfunction "C_C") (pintype "passive"))
      (node (ref "D73") (pin "C") (pinfunction "C_C") (pintype "passive"))
      (node (ref "D89") (pin "C") (pinfunction "C_C") (pintype "passive"))
      (node (ref "D9") (pin "C") (pinfunction "C_C") (pintype "passive"))
      (node (ref "U4") (pin "20") (pinfunction "OUT15_20") (pintype "bidirectional"))
    )
    (net (code "70") (name "ROW9") (class "Default")
      (node (ref "D10") (pin "C") (pinfunction "C_C") (pintype "passive"))
      (node (ref "D106") (pin "C") (pinfunction "C_C") (pintype "passive"))
      (node (ref "D122") (pin "C") (pinfunction "C_C") (pintype "passive"))
      (node (ref "D138") (pin "C") (pinfunction "C_C") (pintype "passive"))
      (node (ref "D154") (pin "C") (pinfunction "C_C") (pintype "passive"))
      (node (ref "D170") (pin "C") (pinfunction "C_C") (pintype "passive"))
      (node (ref "D186") (pin "C") (pinfunction "C_C") (pintype "passive"))
      (node (ref "D202") (pin "C") (pinfunction "C_C") (pintype "passive"))
      (node (ref "D218") (pin "C") (pinfunction "C_C") (pintype "passive"))
      (node (ref "D234") (pin "C") (pinfunction "C_C") (pintype "passive"))
      (node (ref "D250") (pin "C") (pinfunction "C_C") (pintype "passive"))
      (node (ref "D26") (pin "C") (pinfunction "C_C") (pintype "passive"))
      (node (ref "D42") (pin "C") (pinfunction "C_C") (pintype "passive"))
      (node (ref "D58") (pin "C") (pinfunction "C_C") (pintype "passive"))
      (node (ref "D74") (pin "C") (pinfunction "C_C") (pintype "passive"))
      (node (ref "D90") (pin "C") (pinfunction "C_C") (pintype "passive"))
      (node (ref "U4") (pin "19") (pinfunction "OUT14_19") (pintype "bidirectional"))
    )
    (net (code "71") (name "ROW10") (class "Default")
      (node (ref "D107") (pin "C") (pinfunction "C_C") (pintype "passive"))
      (node (ref "D11") (pin "C") (pinfunction "C_C") (pintype "passive"))
      (node (ref "D123") (pin "C") (pinfunction "C_C") (pintype "passive"))
      (node (ref "D139") (pin "C") (pinfunction "C_C") (pintype "passive"))
      (node (ref "D155") (pin "C") (pinfunction "C_C") (pintype "passive"))
      (node (ref "D171") (pin "C") (pinfunction "C_C") (pintype "passive"))
      (node (ref "D187") (pin "C") (pinfunction "C_C") (pintype "passive"))
      (node (ref "D203") (pin "C") (pinfunction "C_C") (pintype "passive"))
      (node (ref "D219") (pin "C") (pinfunction "C_C") (pintype "passive"))
      (node (ref "D235") (pin "C") (pinfunction "C_C") (pintype "passive"))
      (node (ref "D251") (pin "C") (pinfunction "C_C") (pintype "passive"))
      (node (ref "D27") (pin "C") (pinfunction "C_C") (pintype "passive"))
      (node (ref "D43") (pin "C") (pinfunction "C_C") (pintype "passive"))
      (node (ref "D59") (pin "C") (pinfunction "C_C") (pintype "passive"))
      (node (ref "D75") (pin "C") (pinfunction "C_C") (pintype "passive"))
      (node (ref "D91") (pin "C") (pinfunction "C_C") (pintype "passive"))
      (node (ref "U4") (pin "18") (pinfunction "OUT13_18") (pintype "bidirectional"))
    )
    (net (code "72") (name "ROW11") (class "Default")
      (node (ref "D108") (pin "C") (pinfunction "C_C") (pintype "passive"))
      (node (ref "D12") (pin "C") (pinfunction "C_C") (pintype "passive"))
      (node (ref "D124") (pin "C") (pinfunction "C_C") (pintype "passive"))
      (node (ref "D140") (pin "C") (pinfunction "C_C") (pintype "passive"))
      (node (ref "D156") (pin "C") (pinfunction "C_C") (pintype "passive"))
      (node (ref "D172") (pin "C") (pinfunction "C_C") (pintype "passive"))
      (node (ref "D188") (pin "C") (pinfunction "C_C") (pintype "passive"))
      (node (ref "D204") (pin "C") (pinfunction "C_C") (pintype "passive"))
      (node (ref "D220") (pin "C") (pinfunction "C_C") (pintype "passive"))
      (node (ref "D236") (pin "C") (pinfunction "C_C") (pintype "passive"))
      (node (ref "D252") (pin "C") (pinfunction "C_C") (pintype "passive"))
      (node (ref "D28") (pin "C") (pinfunction "C_C") (pintype "passive"))
      (node (ref "D44") (pin "C") (pinfunction "C_C") (pintype "passive"))
      (node (ref "D60") (pin "C") (pinfunction "C_C") (pintype "passive"))
      (node (ref "D76") (pin "C") (pinfunction "C_C") (pintype "passive"))
      (node (ref "D92") (pin "C") (pinfunction "C_C") (pintype "passive"))
      (node (ref "U4") (pin "17") (pinfunction "OUT12_17") (pintype "bidirectional"))
    )
    (net (code "73") (name "ROW12") (class "Default")
      (node (ref "D109") (pin "C") (pinfunction "C_C") (pintype "passive"))
      (node (ref "D125") (pin "C") (pinfunction "C_C") (pintype "passive"))
      (node (ref "D13") (pin "C") (pinfunction "C_C") (pintype "passive"))
      (node (ref "D141") (pin "C") (pinfunction "C_C") (pintype "passive"))
      (node (ref "D157") (pin "C") (pinfunction "C_C") (pintype "passive"))
      (node (ref "D173") (pin "C") (pinfunction "C_C") (pintype "passive"))
      (node (ref "D189") (pin "C") (pinfunction "C_C") (pintype "passive"))
      (node (ref "D205") (pin "C") (pinfunction "C_C") (pintype "passive"))
      (node (ref "D221") (pin "C") (pinfunction "C_C") (pintype "passive"))
      (node (ref "D237") (pin "C") (pinfunction "C_C") (pintype "passive"))
      (node (ref "D253") (pin "C") (pinfunction "C_C") (pintype "passive"))
      (node (ref "D29") (pin "C") (pinfunction "C_C") (pintype "passive"))
      (node (ref "D45") (pin "C") (pinfunction "C_C") (pintype "passive"))
      (node (ref "D61") (pin "C") (pinfunction "C_C") (pintype "passive"))
      (node (ref "D77") (pin "C") (pinfunction "C_C") (pintype "passive"))
      (node (ref "D93") (pin "C") (pinfunction "C_C") (pintype "passive"))
      (node (ref "U4") (pin "16") (pinfunction "OUT11_16") (pintype "bidirectional"))
    )
    (net (code "74") (name "ROW13") (class "Default")
      (node (ref "D110") (pin "C") (pinfunction "C_C") (pintype "passive"))
      (node (ref "D126") (pin "C") (pinfunction "C_C") (pintype "passive"))
      (node (ref "D14") (pin "C") (pinfunction "C_C") (pintype "passive"))
      (node (ref "D142") (pin "C") (pinfunction "C_C") (pintype "passive"))
      (node (ref "D158") (pin "C") (pinfunction "C_C") (pintype "passive"))
      (node (ref "D174") (pin "C") (pinfunction "C_C") (pintype "passive"))
      (node (ref "D190") (pin "C") (pinfunction "C_C") (pintype "passive"))
      (node (ref "D206") (pin "C") (pinfunction "C_C") (pintype "passive"))
      (node (ref "D222") (pin "C") (pinfunction "C_C") (pintype "passive"))
      (node (ref "D238") (pin "C") (pinfunction "C_C") (pintype "passive"))
      (node (ref "D254") (pin "C") (pinfunction "C_C") (pintype "passive"))
      (node (ref "D30") (pin "C") (pinfunction "C_C") (pintype "passive"))
      (node (ref "D46") (pin "C") (pinfunction "C_C") (pintype "passive"))
      (node (ref "D62") (pin "C") (pinfunction "C_C") (pintype "passive"))
      (node (ref "D78") (pin "C") (pinfunction "C_C") (pintype "passive"))
      (node (ref "D94") (pin "C") (pinfunction "C_C") (pintype "passive"))
      (node (ref "U4") (pin "15") (pinfunction "OUT10_15") (pintype "bidirectional"))
    )
    (net (code "75") (name "ROW14") (class "Default")
      (node (ref "D111") (pin "C") (pinfunction "C_C") (pintype "passive"))
      (node (ref "D127") (pin "C") (pinfunction "C_C") (pintype "passive"))
      (node (ref "D143") (pin "C") (pinfunction "C_C") (pintype "passive"))
      (node (ref "D15") (pin "C") (pinfunction "C_C") (pintype "passive"))
      (node (ref "D159") (pin "C") (pinfunction "C_C") (pintype "passive"))
      (node (ref "D175") (pin "C") (pinfunction "C_C") (pintype "passive"))
      (node (ref "D191") (pin "C") (pinfunction "C_C") (pintype "passive"))
      (node (ref "D207") (pin "C") (pinfunction "C_C") (pintype "passive"))
      (node (ref "D223") (pin "C") (pinfunction "C_C") (pintype "passive"))
      (node (ref "D239") (pin "C") (pinfunction "C_C") (pintype "passive"))
      (node (ref "D255") (pin "C") (pinfunction "C_C") (pintype "passive"))
      (node (ref "D31") (pin "C") (pinfunction "C_C") (pintype "passive"))
      (node (ref "D47") (pin "C") (pinfunction "C_C") (pintype "passive"))
      (node (ref "D63") (pin "C") (pinfunction "C_C") (pintype "passive"))
      (node (ref "D79") (pin "C") (pinfunction "C_C") (pintype "passive"))
      (node (ref "D95") (pin "C") (pinfunction "C_C") (pintype "passive"))
      (node (ref "U4") (pin "14") (pinfunction "OUT9_14") (pintype "bidirectional"))
    )
    (net (code "76") (name "ROW15") (class "Default")
      (node (ref "D112") (pin "C") (pinfunction "C_C") (pintype "passive"))
      (node (ref "D128") (pin "C") (pinfunction "C_C") (pintype "passive"))
      (node (ref "D144") (pin "C") (pinfunction "C_C") (pintype "passive"))
      (node (ref "D16") (pin "C") (pinfunction "C_C") (pintype "passive"))
      (node (ref "D160") (pin "C") (pinfunction "C_C") (pintype "passive"))
      (node (ref "D176") (pin "C") (pinfunction "C_C") (pintype "passive"))
      (node (ref "D192") (pin "C") (pinfunction "C_C") (pintype "passive"))
      (node (ref "D208") (pin "C") (pinfunction "C_C") (pintype "passive"))
      (node (ref "D224") (pin "C") (pinfunction "C_C") (pintype "passive"))
      (node (ref "D240") (pin "C") (pinfunction "C_C") (pintype "passive"))
      (node (ref "D256") (pin "C") (pinfunction "C_C") (pintype "passive"))
      (node (ref "D32") (pin "C") (pinfunction "C_C") (pintype "passive"))
      (node (ref "D48") (pin "C") (pinfunction "C_C") (pintype "passive"))
      (node (ref "D64") (pin "C") (pinfunction "C_C") (pintype "passive"))
      (node (ref "D80") (pin "C") (pinfunction "C_C") (pintype "passive"))
      (node (ref "D96") (pin "C") (pinfunction "C_C") (pintype "passive"))
      (node (ref "U4") (pin "13") (pinfunction "OUT8_13") (pintype "bidirectional"))
    )
    (net (code "77") (name "RXD0") (class "Default")
      (node (ref "RX") (pin "TP") (pinfunction "TP_TP") (pintype "input"))
      (node (ref "U1") (pin "14") (pinfunction "PC2_14") (pintype "bidirectional"))
    )
    (net (code "78") (name "TXD0") (class "Default")
      (node (ref "TX") (pin "TP") (pinfunction "TP_TP") (pintype "input"))
      (node (ref "U1") (pin "13") (pinfunction "PC3_13") (pintype "bidirectional"))
    )
    (net (code "79") (name "V+") (class "Default")
      (node (ref "C1") (pin "1") (pinfunction "1_1") (pintype "passive"))
      (node (ref "C2") (pin "1") (pinfunction "1_1") (pintype "passive"))
      (node (ref "FB1") (pin "1") (pinfunction "P$1_1") (pintype "bidirectional"))
      (node (ref "U1") (pin "32") (pinfunction "AVCC_32") (pintype "bidirectional"))
    )
    (net (code "80") (name "VDD") (class "Default")
      (node (ref "C3") (pin "1") (pinfunction "1_1") (pintype "passive"))
      (node (ref "C6") (pin "1") (pinfunction "1_1") (pintype "passive"))
      (node (ref "C9") (pin "1") (pinfunction "1_1") (pintype "passive"))
      (node (ref "FB1") (pin "2") (pinfunction "P$2_2") (pintype "bidirectional"))
      (node (ref "J1") (pin "2") (pinfunction "VCC_2") (pintype "bidirectional"))
      (node (ref "R2") (pin "1") (pinfunction "1_1") (pintype "passive"))
      (node (ref "R38") (pin "2") (pinfunction "2_2") (pintype "passive"))
      (node (ref "R39") (pin "2") (pinfunction "2_2") (pintype "passive"))
      (node (ref "SWT1") (pin "2") (pinfunction "P$2_2") (pintype "bidirectional"))
      (node (ref "U1") (pin "17") (pinfunction "VCC_17") (pintype "bidirectional"))
      (node (ref "U3") (pin "7") (pinfunction "~{HOLD}_7") (pintype "bidirectional"))
      (node (ref "U3") (pin "8") (pinfunction "VCC_8") (pintype "bidirectional"))
      (node (ref "U4") (pin "24") (pinfunction "VDD_24") (pintype "bidirectional"))
    )
    (net (code "81") (name "unconnected-(J1-Pad3)") (class "Default")
      (node (ref "J1") (pin "3") (pinfunction "3_3") (pintype "bidirectional"))
    )
    (net (code "82") (name "unconnected-(J1-Pad4)") (class "Default")
      (node (ref "J1") (pin "4") (pinfunction "4_4") (pintype "bidirectional"))
    )
    (net (code "83") (name "unconnected-(TP1-PadTP)") (class "Default")
      (node (ref "TP1") (pin "TP") (pinfunction "TP_TP") (pintype "input"))
    )
    (net (code "84") (name "unconnected-(TP15-PadTP)") (class "Default")
      (node (ref "TP15") (pin "TP") (pinfunction "TP_TP") (pintype "input"))
    )
    (net (code "85") (name "unconnected-(U1-PC0-Pad16)") (class "Default")
      (node (ref "U1") (pin "16") (pinfunction "PC0_16") (pintype "bidirectional"))
    )
    (net (code "86") (name "unconnected-(U1-PC1-Pad15)") (class "Default")
      (node (ref "U1") (pin "15") (pinfunction "PC1_15") (pintype "bidirectional"))
    )
    (net (code "87") (name "unconnected-(U1-PD5-Pad23)") (class "Default")
      (node (ref "U1") (pin "23") (pinfunction "PD5_23") (pintype "bidirectional"))
    )
    (net (code "88") (name "unconnected-(U1-PD6-Pad22)") (class "Default")
      (node (ref "U1") (pin "22") (pinfunction "PD6_22") (pintype "bidirectional"))
    )
    (net (code "89") (name "unconnected-(U1-PD7-Pad21)") (class "Default")
      (node (ref "U1") (pin "21") (pinfunction "PD7_21") (pintype "bidirectional"))
    )
    (net (code "90") (name "unconnected-(U4-SDO-Pad22)") (class "Default")
      (node (ref "U4") (pin "22") (pinfunction "SDO_22") (pintype "bidirectional"))
    )
  )
)
